# LE.net
KiCad netlist of a schematic drawn in EAGLE
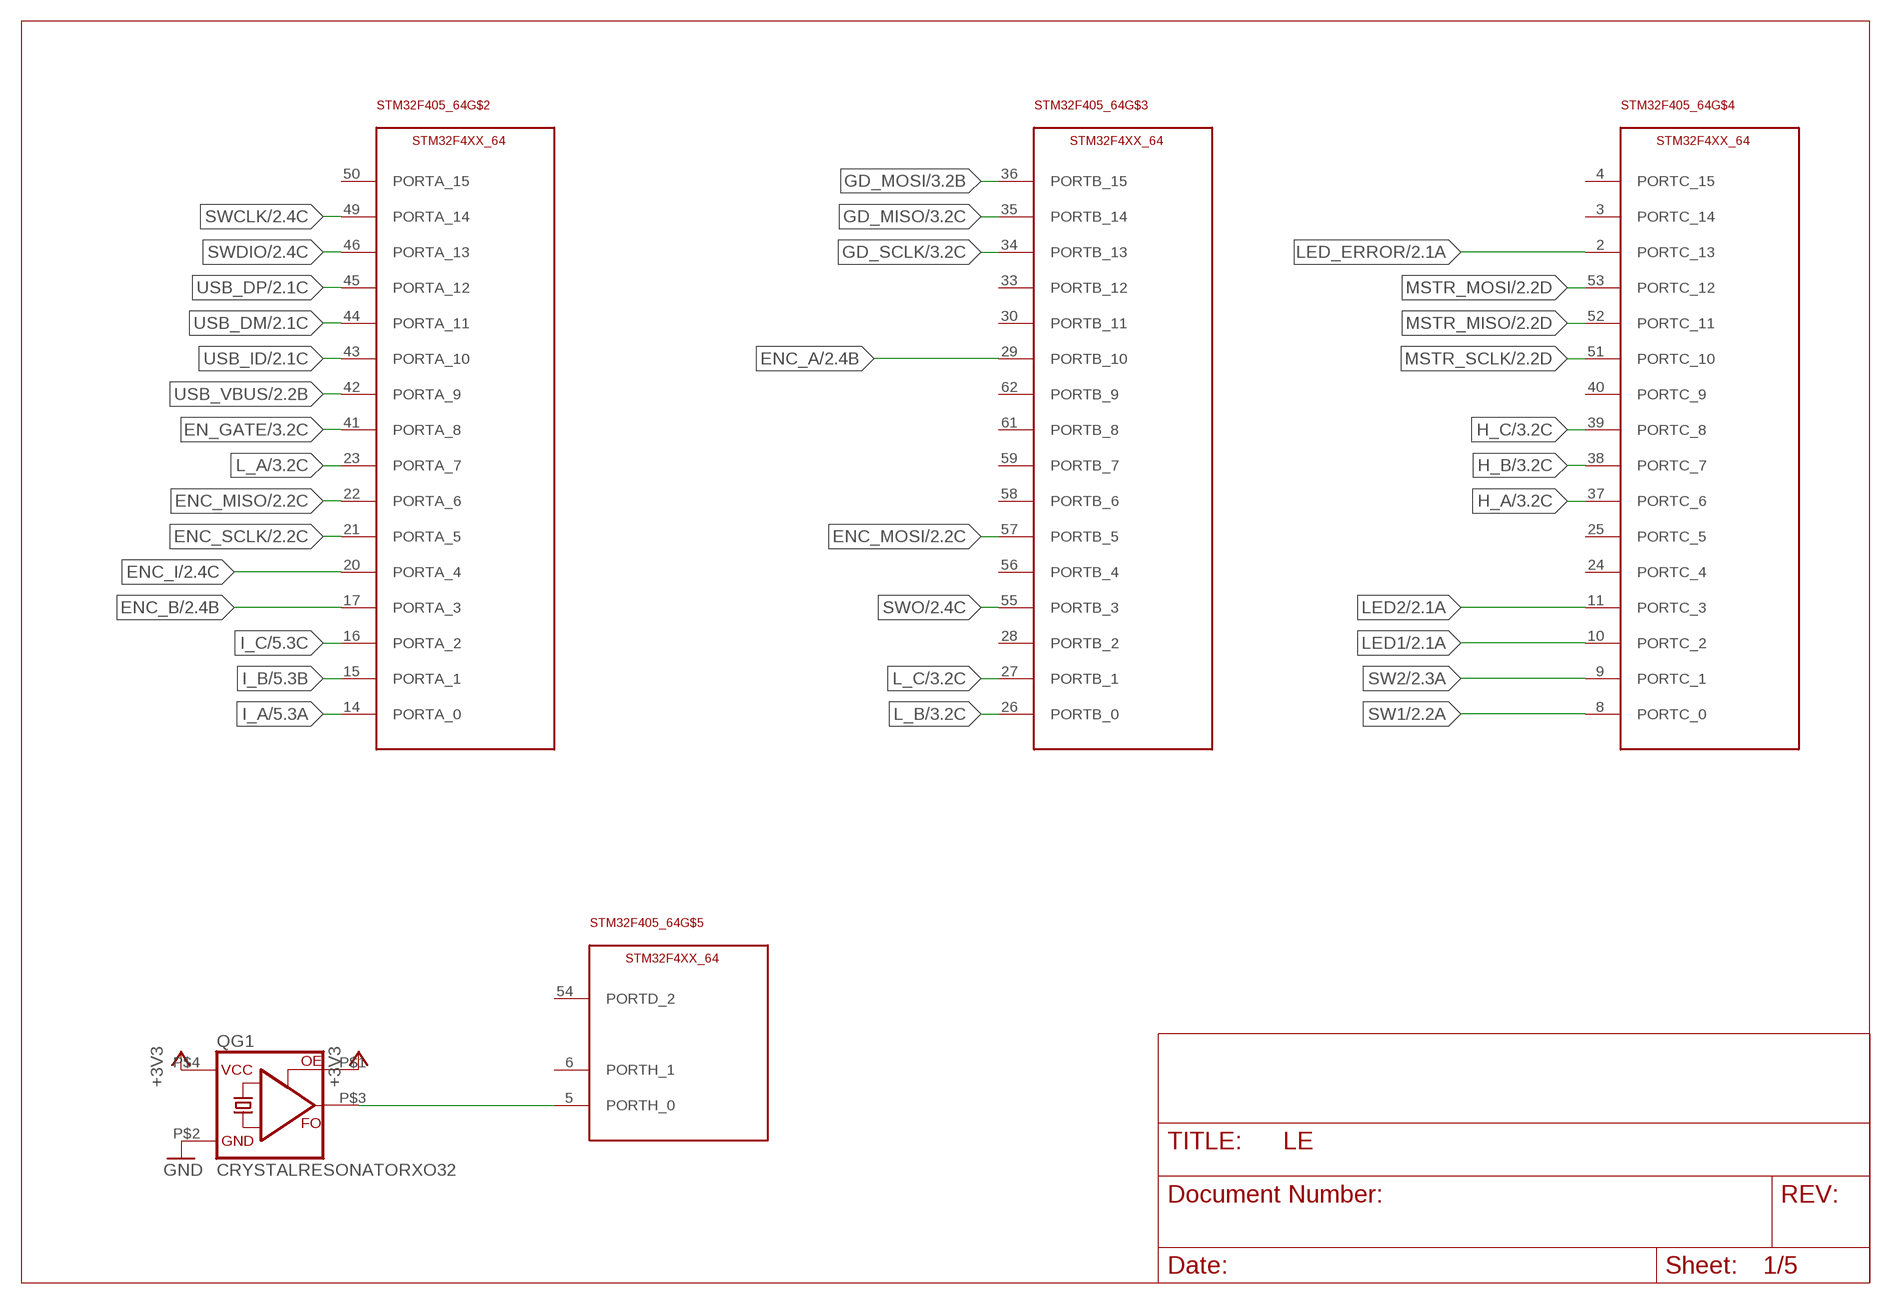
[diagram p0: schematic, sheet 1]
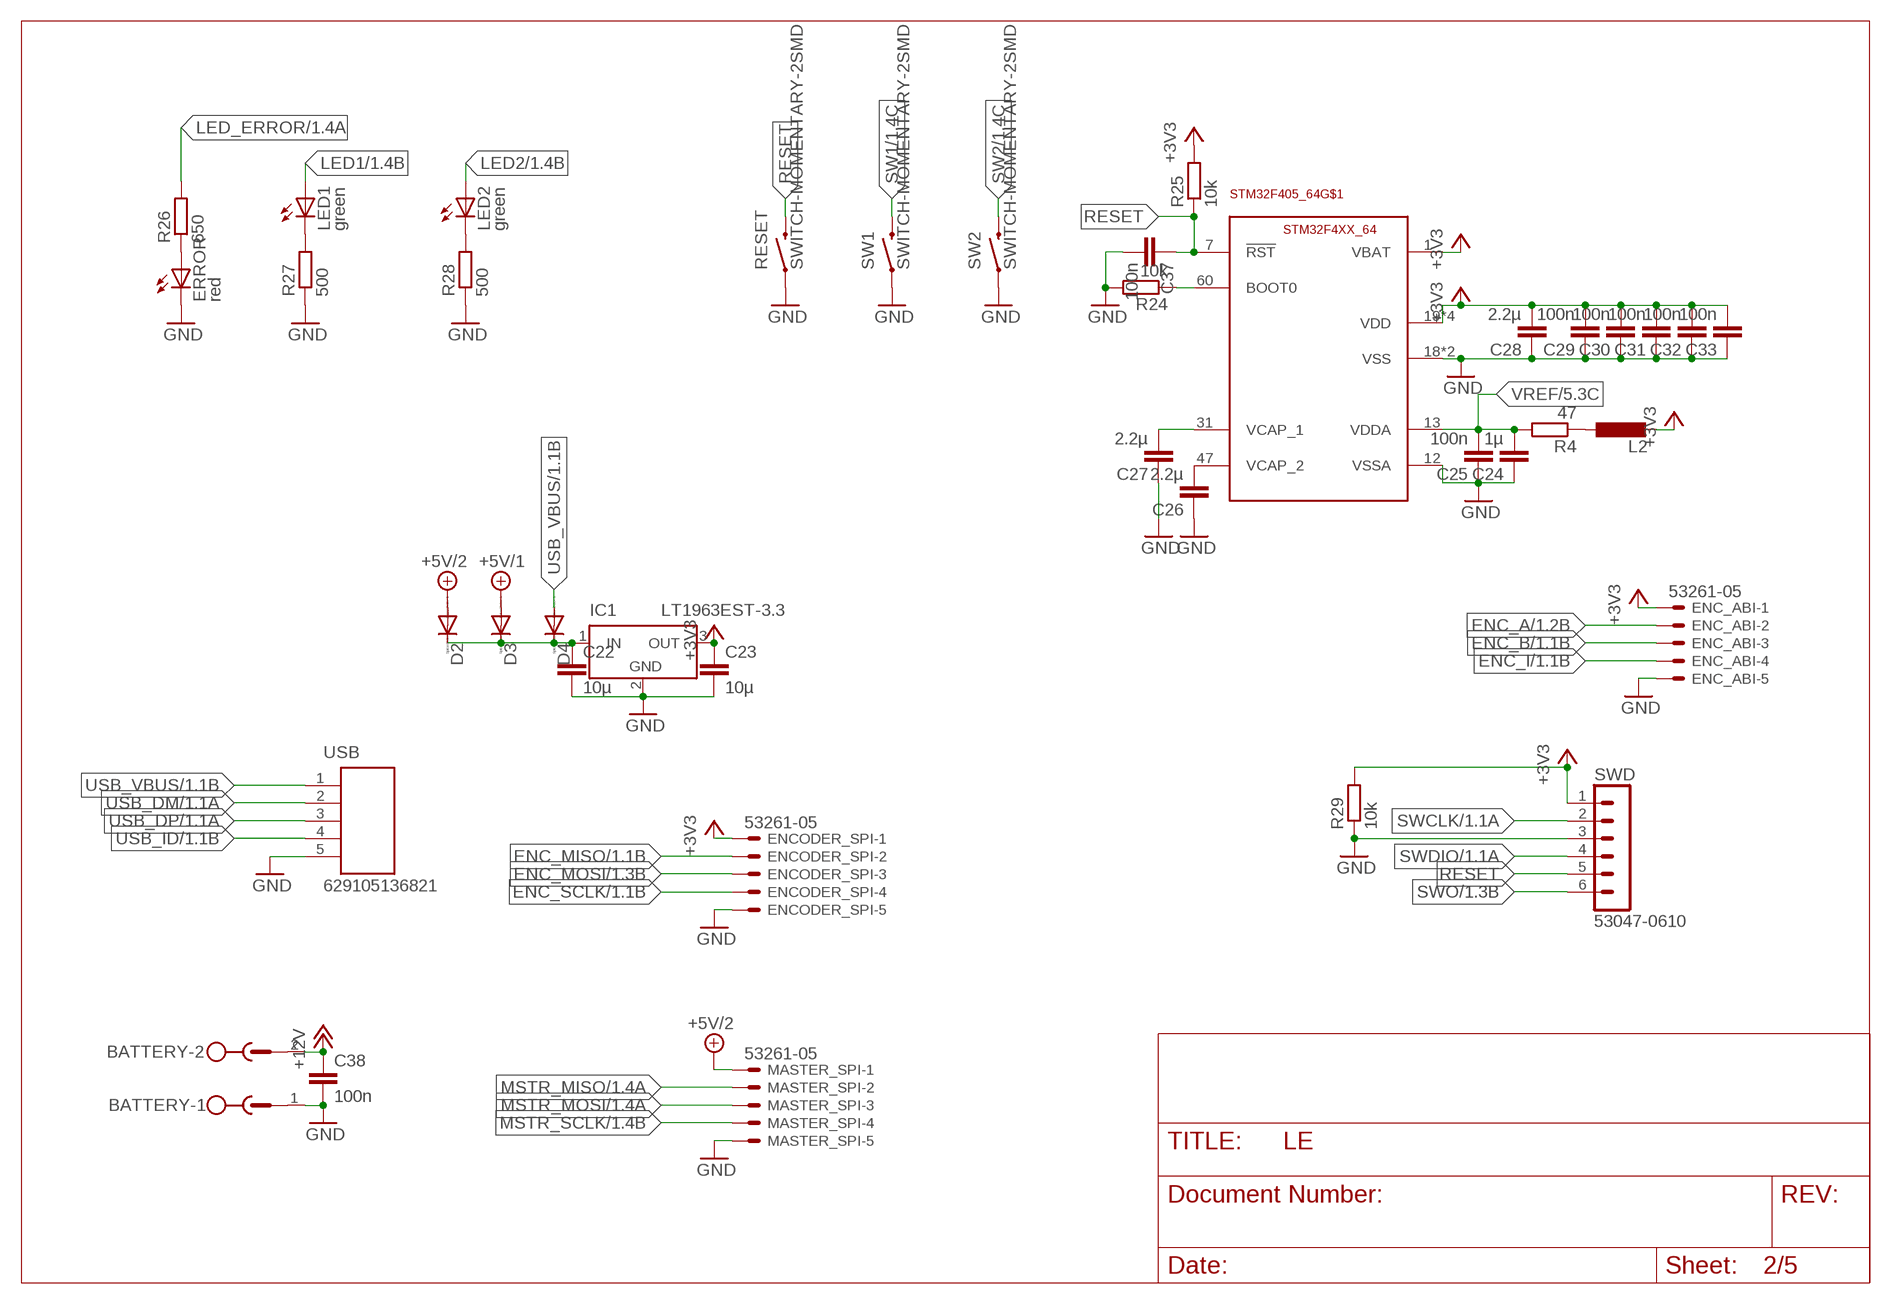
[diagram p1: schematic, sheet 2]
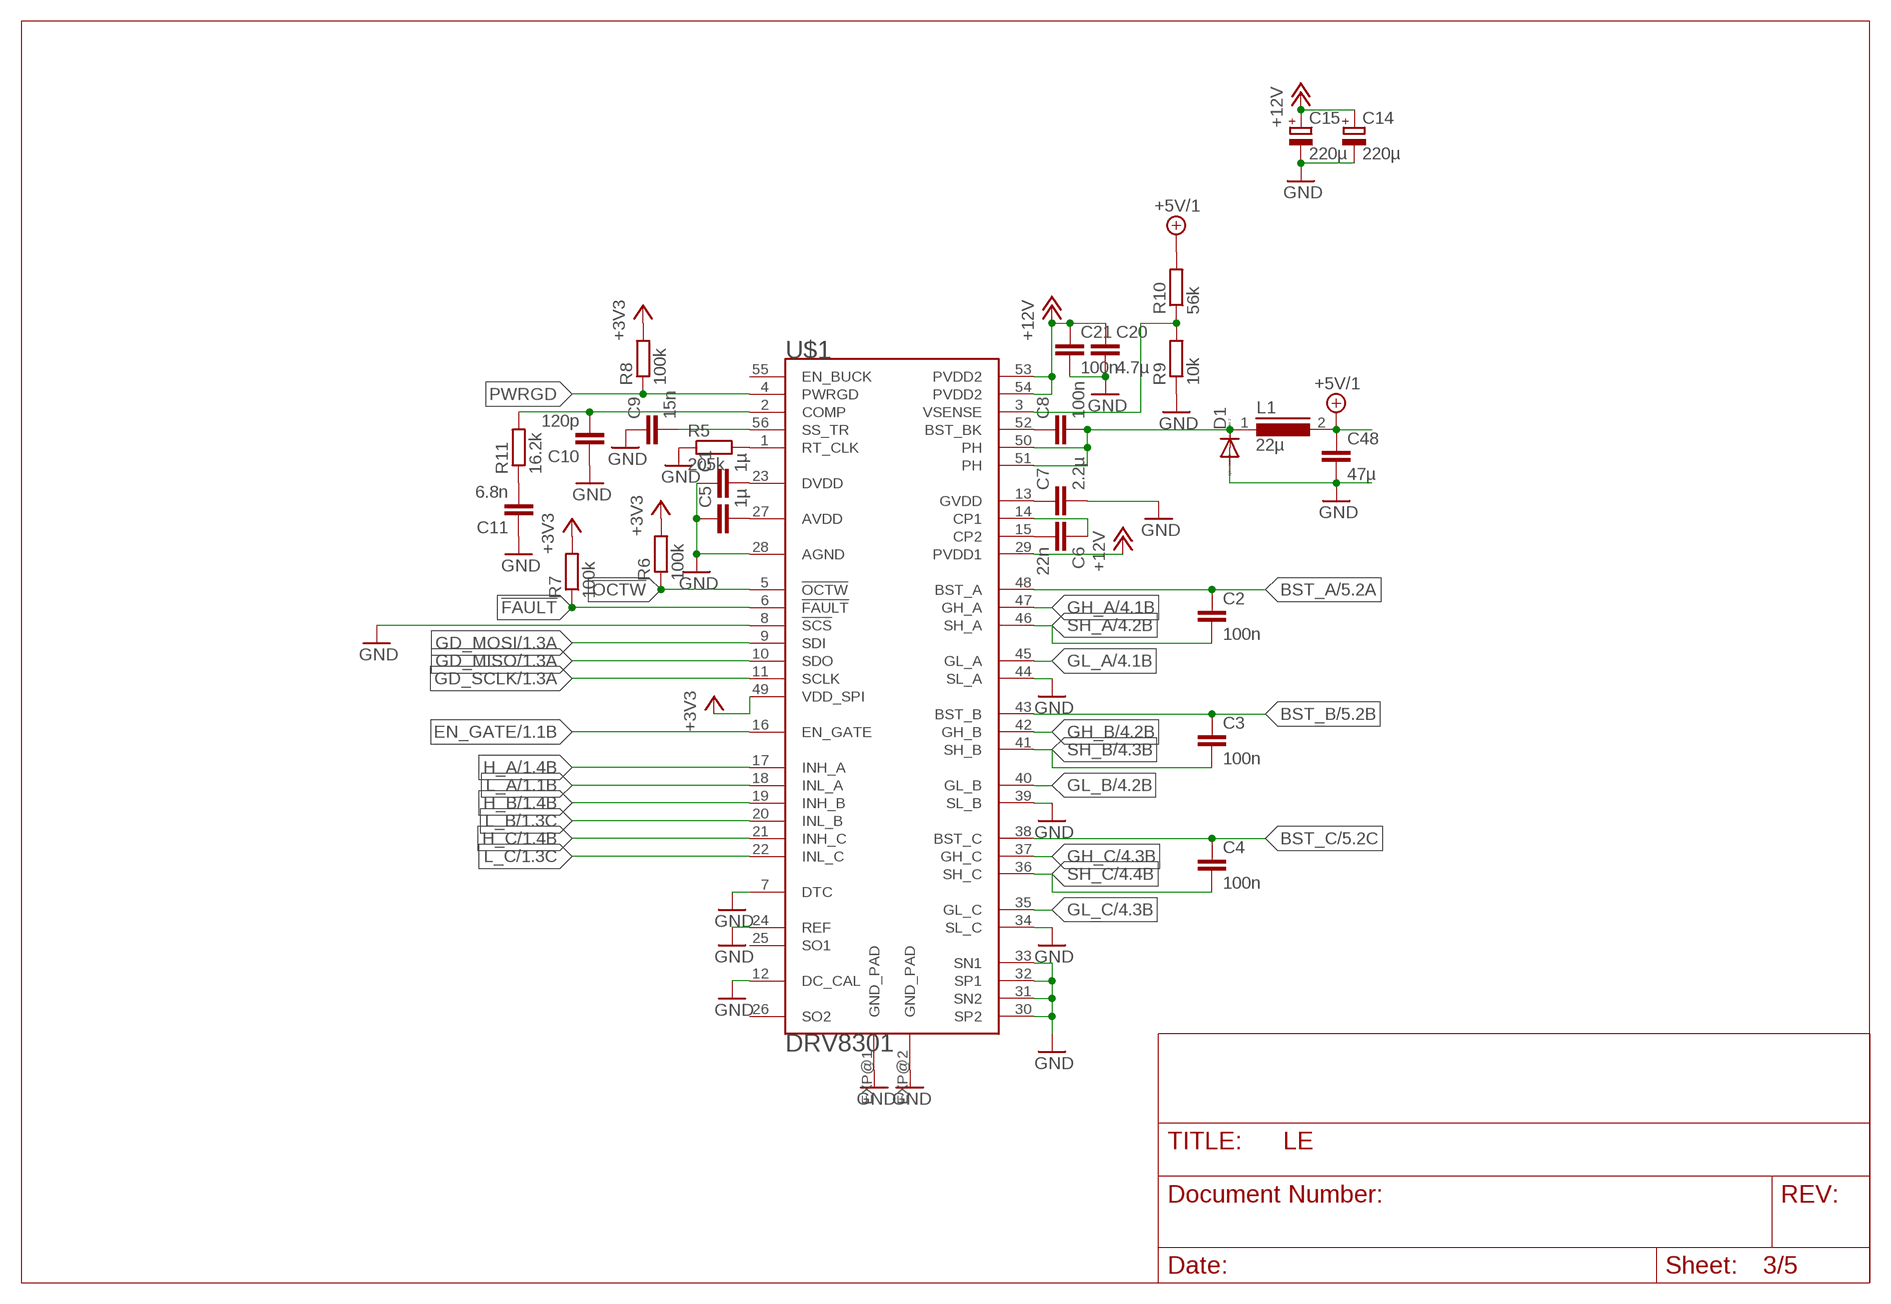
[diagram p2: schematic, sheet 3]
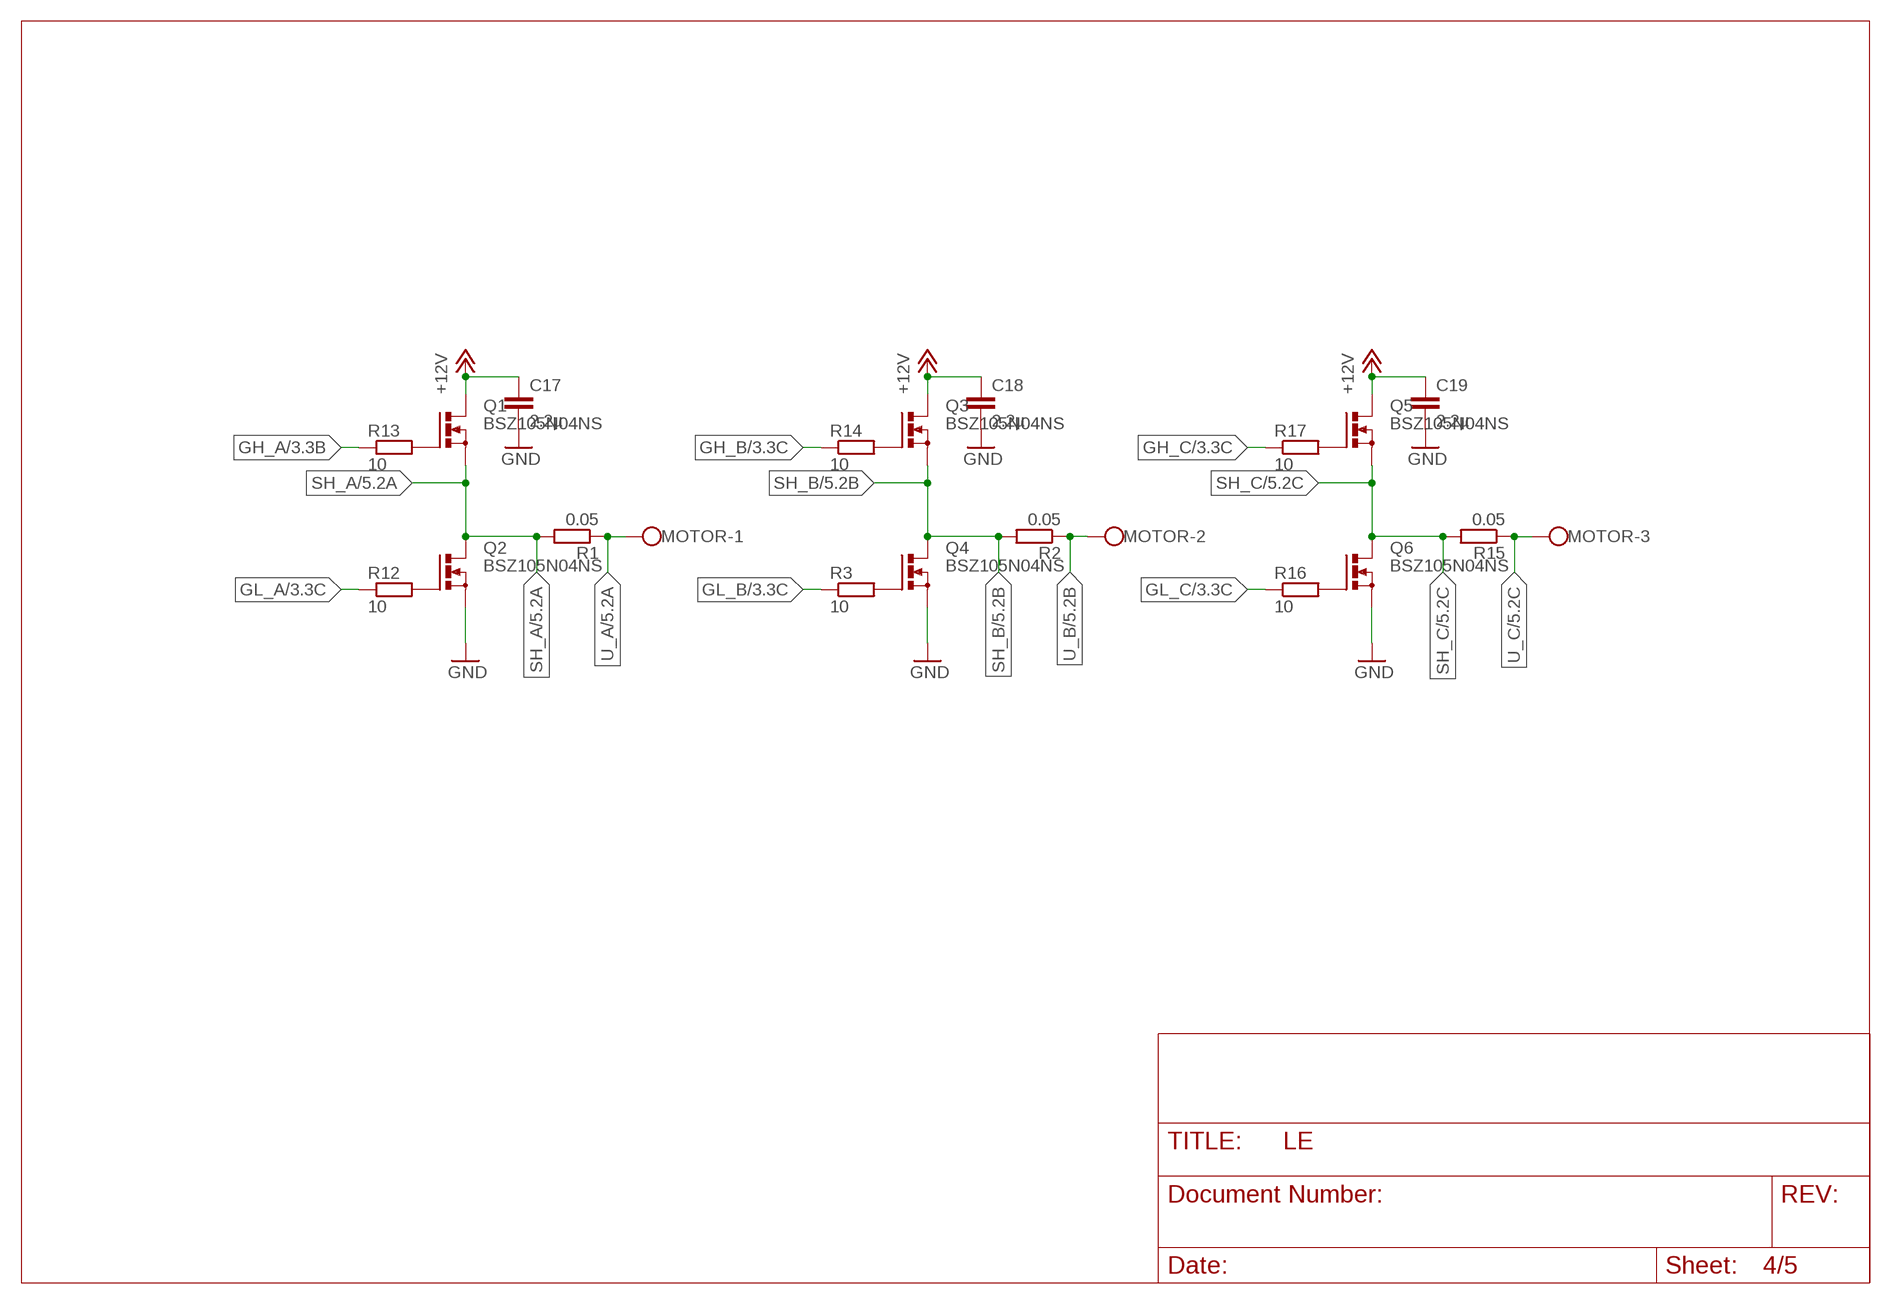
[diagram p3: schematic, sheet 4]
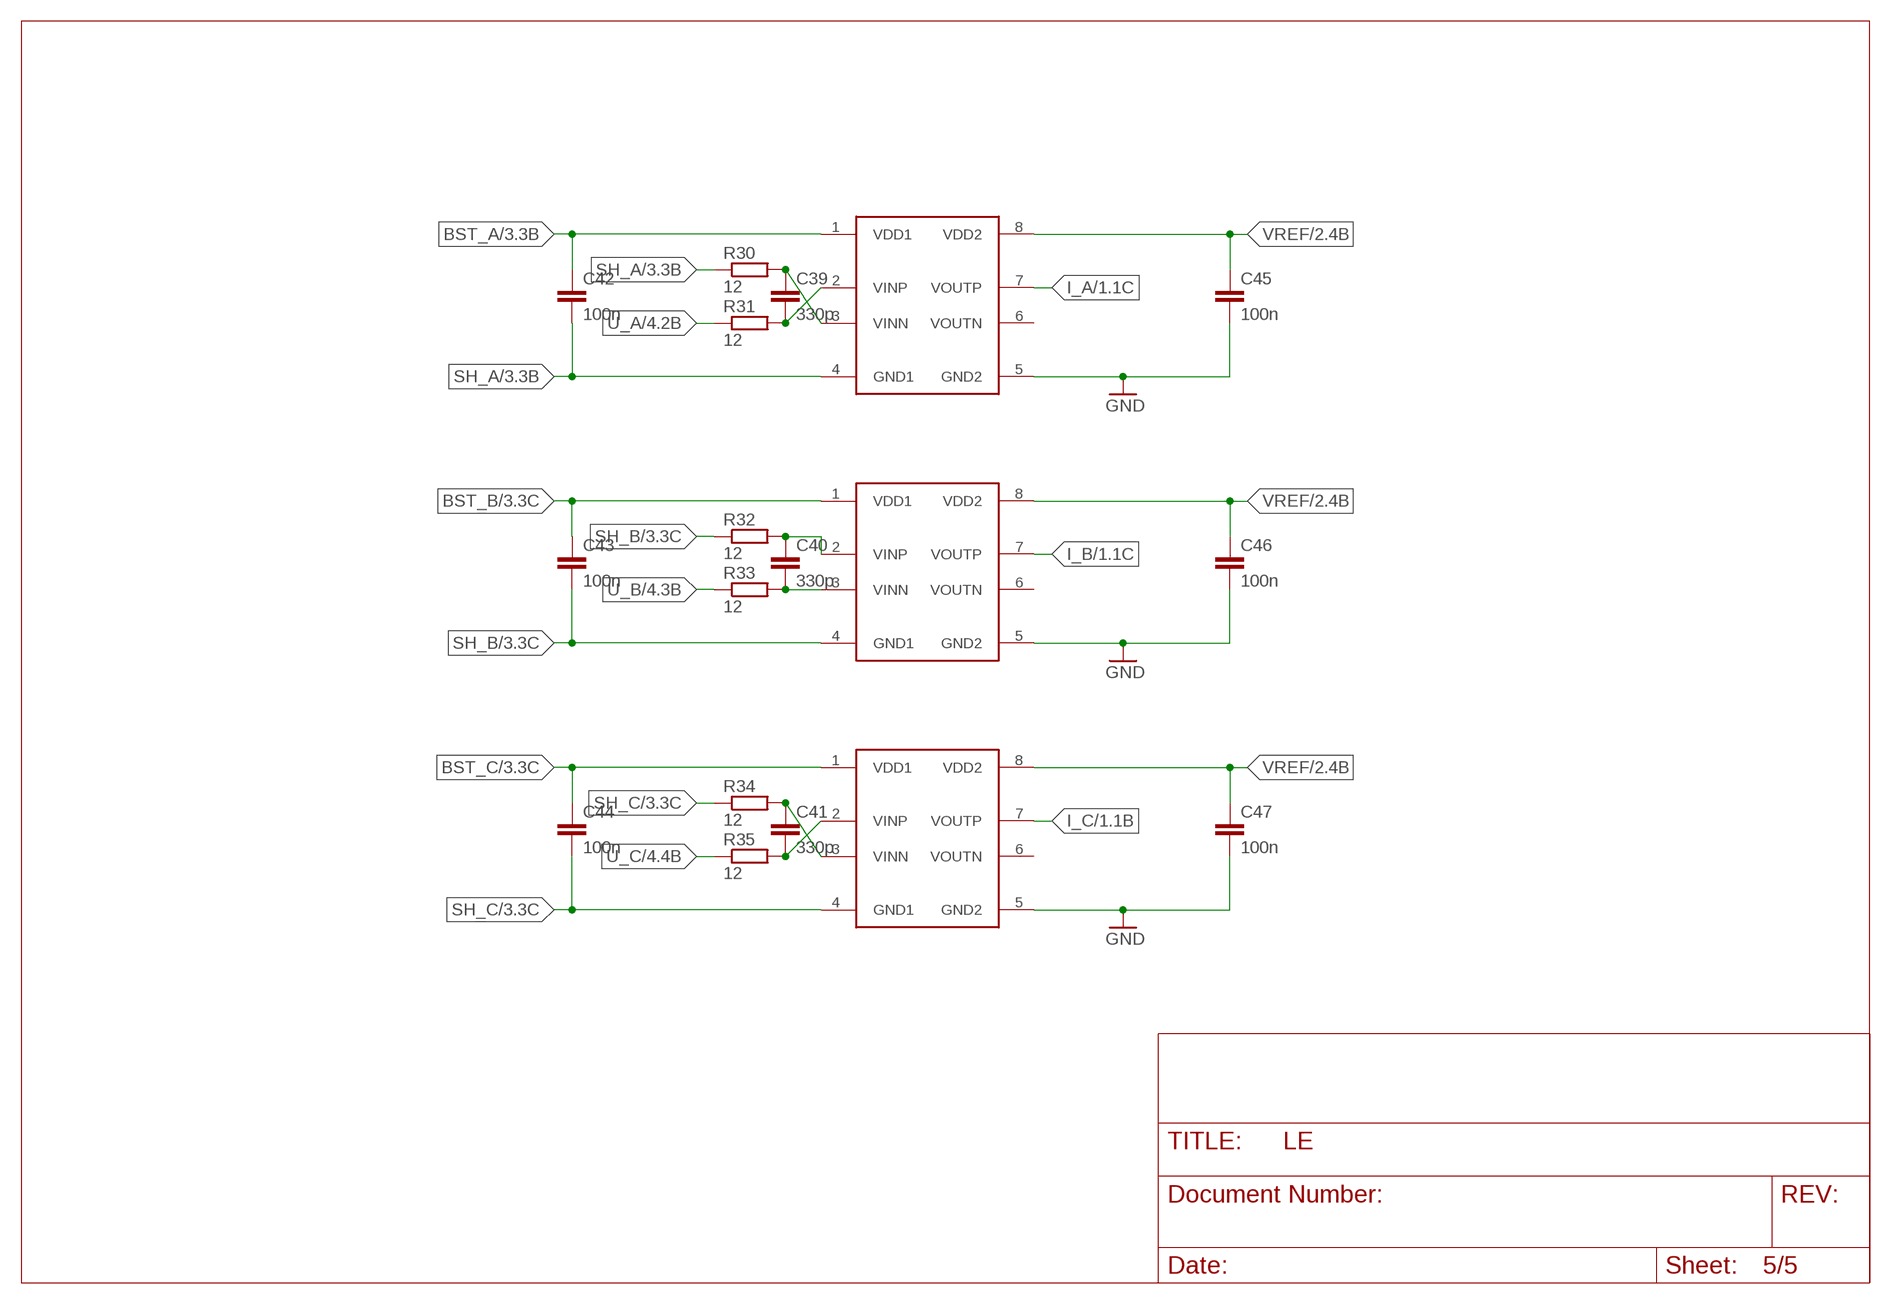
[diagram p4: schematic, sheet 5]

(export (version "E")
  (design (tool "Eeschema 10.0.6"))
  (components
    (comp (ref "C17")
      (value "2.2µ")
      (footprint "eagle-import:C0805")
      (libsource (lib "eagle-import") (part "C-EUC0805"))
    )
    (comp (ref "C18")
      (value "2.2µ")
      (footprint "eagle-import:C0805")
      (libsource (lib "eagle-import") (part "C-EUC0805"))
    )
    (comp (ref "C19")
      (value "2.2µ")
      (footprint "eagle-import:C0805")
      (libsource (lib "eagle-import") (part "C-EUC0805"))
    )
    (comp (ref "MOTOR")
      (value "W237-103")
      (footprint "eagle-import:W237-103")
      (fields (field (name "MPN") "237-103"))
      (libsource (lib "eagle-import") (part "W237-103"))
    )
    (comp (ref "Q1")
      (value "BSZ105N04NS")
      (footprint "eagle-import:PG-TDSON-8")
      (libsource (lib "eagle-import") (part "BSZ105N04NS"))
    )
    (comp (ref "Q2")
      (value "BSZ105N04NS")
      (footprint "eagle-import:PG-TDSON-8")
      (libsource (lib "eagle-import") (part "BSZ105N04NS"))
    )
    (comp (ref "Q3")
      (value "BSZ105N04NS")
      (footprint "eagle-import:PG-TDSON-8")
      (libsource (lib "eagle-import") (part "BSZ105N04NS"))
    )
    (comp (ref "Q4")
      (value "BSZ105N04NS")
      (footprint "eagle-import:PG-TDSON-8")
      (libsource (lib "eagle-import") (part "BSZ105N04NS"))
    )
    (comp (ref "Q5")
      (value "BSZ105N04NS")
      (footprint "eagle-import:PG-TDSON-8")
      (libsource (lib "eagle-import") (part "BSZ105N04NS"))
    )
    (comp (ref "Q6")
      (value "BSZ105N04NS")
      (footprint "eagle-import:PG-TDSON-8")
      (libsource (lib "eagle-import") (part "BSZ105N04NS"))
    )
    (comp (ref "R1")
      (value "0.05")
      (footprint "eagle-import:R1206")
      (libsource (lib "eagle-import") (part "R-EU_R1206"))
    )
    (comp (ref "R2")
      (value "0.05")
      (footprint "eagle-import:R1206")
      (libsource (lib "eagle-import") (part "R-EU_R1206"))
    )
    (comp (ref "R3")
      (value "10")
      (footprint "eagle-import:R1206")
      (libsource (lib "eagle-import") (part "R-EU_R1206"))
    )
    (comp (ref "R12")
      (value "10")
      (footprint "eagle-import:R1206")
      (libsource (lib "eagle-import") (part "R-EU_R1206"))
    )
    (comp (ref "R13")
      (value "10")
      (footprint "eagle-import:R0805")
      (libsource (lib "eagle-import") (part "R-EU_R0805"))
    )
    (comp (ref "R14")
      (value "10")
      (footprint "eagle-import:R0805")
      (libsource (lib "eagle-import") (part "R-EU_R0805"))
    )
    (comp (ref "R15")
      (value "0.05")
      (footprint "eagle-import:R1206")
      (libsource (lib "eagle-import") (part "R-EU_R1206"))
    )
    (comp (ref "R16")
      (value "10")
      (footprint "eagle-import:R1206")
      (libsource (lib "eagle-import") (part "R-EU_R1206"))
    )
    (comp (ref "R17")
      (value "10")
      (footprint "eagle-import:R0805")
      (libsource (lib "eagle-import") (part "R-EU_R0805"))
    )
    (comp (ref "C39")
      (value "330p")
      (footprint "eagle-import:C0805")
      (libsource (lib "eagle-import") (part "C-EUC0805"))
    )
    (comp (ref "C40")
      (value "330p")
      (footprint "eagle-import:C0805")
      (libsource (lib "eagle-import") (part "C-EUC0805"))
    )
    (comp (ref "C41")
      (value "330p")
      (footprint "eagle-import:C0805")
      (libsource (lib "eagle-import") (part "C-EUC0805"))
    )
    (comp (ref "C42")
      (value "100n")
      (footprint "eagle-import:C1206")
      (libsource (lib "eagle-import") (part "C-EUC1206"))
    )
    (comp (ref "C43")
      (value "100n")
      (footprint "eagle-import:C1206")
      (libsource (lib "eagle-import") (part "C-EUC1206"))
    )
    (comp (ref "C44")
      (value "100n")
      (footprint "eagle-import:C1206")
      (libsource (lib "eagle-import") (part "C-EUC1206"))
    )
    (comp (ref "C45")
      (value "100n")
      (footprint "eagle-import:C1206")
      (libsource (lib "eagle-import") (part "C-EUC1206"))
    )
    (comp (ref "C46")
      (value "100n")
      (footprint "eagle-import:C1206")
      (libsource (lib "eagle-import") (part "C-EUC1206"))
    )
    (comp (ref "C47")
      (value "100n")
      (footprint "eagle-import:C1206")
      (libsource (lib "eagle-import") (part "C-EUC1206"))
    )
    (comp (ref "R30")
      (value "12")
      (footprint "eagle-import:R0805")
      (libsource (lib "eagle-import") (part "R-EU_R0805"))
    )
    (comp (ref "R31")
      (value "12")
      (footprint "eagle-import:R0805")
      (libsource (lib "eagle-import") (part "R-EU_R0805"))
    )
    (comp (ref "R32")
      (value "12")
      (footprint "eagle-import:R0805")
      (libsource (lib "eagle-import") (part "R-EU_R0805"))
    )
    (comp (ref "R33")
      (value "12")
      (footprint "eagle-import:R0805")
      (libsource (lib "eagle-import") (part "R-EU_R0805"))
    )
    (comp (ref "R34")
      (value "12")
      (footprint "eagle-import:R0805")
      (libsource (lib "eagle-import") (part "R-EU_R0805"))
    )
    (comp (ref "R35")
      (value "12")
      (footprint "eagle-import:R0805")
      (libsource (lib "eagle-import") (part "R-EU_R0805"))
    )
    (comp (ref "U$2")
      (value "AMC1200")
      (footprint "eagle-import:SOIC8")
      (libsource (lib "eagle-import") (part "AMC1200"))
    )
    (comp (ref "U$3")
      (value "AMC1200")
      (footprint "eagle-import:SOIC8")
      (libsource (lib "eagle-import") (part "AMC1200"))
    )
    (comp (ref "U$4")
      (value "AMC1200")
      (footprint "eagle-import:SOIC8")
      (libsource (lib "eagle-import") (part "AMC1200"))
    )
    (comp (ref "BATTERY")
      (value "MSTBV2")
      (footprint "eagle-import:MSTBV2")
      (libsource (lib "eagle-import") (part "MSTBV2"))
    )
    (comp (ref "C22")
      (value "10µ")
      (footprint "eagle-import:C0805")
      (libsource (lib "eagle-import") (part "C-EUC0805"))
    )
    (comp (ref "C23")
      (value "10µ")
      (footprint "eagle-import:C0805")
      (libsource (lib "eagle-import") (part "C-EUC0805"))
    )
    (comp (ref "C24")
      (value "1µ")
      (footprint "eagle-import:C0805")
      (libsource (lib "eagle-import") (part "C-EUC0805"))
    )
    (comp (ref "C25")
      (value "100n")
      (footprint "eagle-import:C0805")
      (libsource (lib "eagle-import") (part "C-EUC0805"))
    )
    (comp (ref "C26")
      (value "2.2µ")
      (footprint "eagle-import:C0805")
      (libsource (lib "eagle-import") (part "C-EUC0805"))
    )
    (comp (ref "C27")
      (value "2.2µ")
      (footprint "eagle-import:C0805")
      (libsource (lib "eagle-import") (part "C-EUC0805"))
    )
    (comp (ref "C28")
      (value "2.2µ")
      (footprint "eagle-import:C0805")
      (libsource (lib "eagle-import") (part "C-EUC0805"))
    )
    (comp (ref "C29")
      (value "100n")
      (footprint "eagle-import:C0805")
      (libsource (lib "eagle-import") (part "C-EUC0805"))
    )
    (comp (ref "C30")
      (value "100n")
      (footprint "eagle-import:C0805")
      (libsource (lib "eagle-import") (part "C-EUC0805"))
    )
    (comp (ref "C31")
      (value "100n")
      (footprint "eagle-import:C0805")
      (libsource (lib "eagle-import") (part "C-EUC0805"))
    )
    (comp (ref "C32")
      (value "100n")
      (footprint "eagle-import:C0805")
      (libsource (lib "eagle-import") (part "C-EUC0805"))
    )
    (comp (ref "C33")
      (value "100n")
      (footprint "eagle-import:C0805")
      (libsource (lib "eagle-import") (part "C-EUC0805"))
    )
    (comp (ref "C37")
      (value "100n")
      (footprint "eagle-import:C0805")
      (libsource (lib "eagle-import") (part "C-EUC0805"))
    )
    (comp (ref "C38")
      (value "100n")
      (footprint "eagle-import:C0805")
      (libsource (lib "eagle-import") (part "C-EUC0805"))
    )
    (comp (ref "D2")
      (value "DIODE-DO214AC")
      (footprint "eagle-import:DO214AC")
      (libsource (lib "eagle-import") (part "DIODE-DO214AC"))
    )
    (comp (ref "D3")
      (value "DIODE-DO214AC")
      (footprint "eagle-import:DO214AC")
      (libsource (lib "eagle-import") (part "DIODE-DO214AC"))
    )
    (comp (ref "D4")
      (value "DIODE-DO214AC")
      (footprint "eagle-import:DO214AC")
      (libsource (lib "eagle-import") (part "DIODE-DO214AC"))
    )
    (comp (ref "ENCODER_SPI")
      (value "53261-05")
      (footprint "eagle-import:53261-05")
      (libsource (lib "eagle-import") (part "53?-05261"))
    )
    (comp (ref "ENC_ABI")
      (value "53261-05")
      (footprint "eagle-import:53261-05")
      (libsource (lib "eagle-import") (part "53?-05261"))
    )
    (comp (ref "ERROR")
      (value "red")
      (footprint "eagle-import:CHIP-LED0805")
      (libsource (lib "eagle-import") (part "LEDCHIP-LED0805"))
    )
    (comp (ref "IC1")
      (value "LT1963EST-3.3")
      (footprint "eagle-import:SOT223")
      (libsource (lib "eagle-import") (part "LT1963EST-3.3"))
    )
    (comp (ref "L2")
      (value "L-EUL2012C")
      (footprint "eagle-import:L2012C")
      (libsource (lib "eagle-import") (part "L-EUL2012C"))
    )
    (comp (ref "LED1")
      (value "green")
      (footprint "eagle-import:CHIP-LED0805")
      (libsource (lib "eagle-import") (part "LEDCHIP-LED0805"))
    )
    (comp (ref "LED2")
      (value "green")
      (footprint "eagle-import:CHIP-LED0805")
      (libsource (lib "eagle-import") (part "LEDCHIP-LED0805"))
    )
    (comp (ref "MASTER_SPI")
      (value "53261-05")
      (footprint "eagle-import:53261-05")
      (libsource (lib "eagle-import") (part "53?-05261"))
    )
    (comp (ref "R4")
      (value "47")
      (footprint "eagle-import:R0805")
      (libsource (lib "eagle-import") (part "R-EU_R0805"))
    )
    (comp (ref "R24")
      (value "10k")
      (footprint "eagle-import:R0805")
      (libsource (lib "eagle-import") (part "R-EU_R0805"))
    )
    (comp (ref "R25")
      (value "10k")
      (footprint "eagle-import:R0805")
      (libsource (lib "eagle-import") (part "R-EU_R0805"))
    )
    (comp (ref "R26")
      (value "650")
      (footprint "eagle-import:R0805")
      (libsource (lib "eagle-import") (part "R-EU_R0805"))
    )
    (comp (ref "R27")
      (value "500")
      (footprint "eagle-import:R0805")
      (libsource (lib "eagle-import") (part "R-EU_R0805"))
    )
    (comp (ref "R28")
      (value "500")
      (footprint "eagle-import:R0805")
      (libsource (lib "eagle-import") (part "R-EU_R0805"))
    )
    (comp (ref "R29")
      (value "10k")
      (footprint "eagle-import:R0805")
      (libsource (lib "eagle-import") (part "R-EU_R0805"))
    )
    (comp (ref "RESET")
      (value "SWITCH-MOMENTARY-2SMD")
      (footprint "eagle-import:TACTILE-SWITCH-SMD")
      (libsource (lib "eagle-import") (part "SWITCH-MOMENTARY-2SMD"))
    )
    (comp (ref "STM32F405_64")
      (value "STM32F4XX_64")
      (footprint "eagle-import:TQFP64")
      (libsource (lib "eagle-import") (part "STM32F4XX_64"))
    )
    (comp (ref "SW1")
      (value "SWITCH-MOMENTARY-2SMD")
      (footprint "eagle-import:TACTILE-SWITCH-SMD")
      (libsource (lib "eagle-import") (part "SWITCH-MOMENTARY-2SMD"))
    )
    (comp (ref "SW2")
      (value "SWITCH-MOMENTARY-2SMD")
      (footprint "eagle-import:TACTILE-SWITCH-SMD")
      (libsource (lib "eagle-import") (part "SWITCH-MOMENTARY-2SMD"))
    )
    (comp (ref "SWD")
      (value "53047-0610")
      (footprint "eagle-import:53047-0610")
      (libsource (lib "eagle-import") (part "53047-0610"))
    )
    (comp (ref "USB")
      (value "629105136821")
      (footprint "eagle-import:629105136821")
      (libsource (lib "eagle-import") (part "629105136821"))
    )
    (comp (ref "C1")
      (value "1µ")
      (footprint "eagle-import:C0805")
      (libsource (lib "eagle-import") (part "C-EUC0805"))
    )
    (comp (ref "C2")
      (value "100n")
      (footprint "eagle-import:C0805")
      (libsource (lib "eagle-import") (part "C-EUC0805"))
    )
    (comp (ref "C3")
      (value "100n")
      (footprint "eagle-import:C0805")
      (libsource (lib "eagle-import") (part "C-EUC0805"))
    )
    (comp (ref "C4")
      (value "100n")
      (footprint "eagle-import:C0805")
      (libsource (lib "eagle-import") (part "C-EUC0805"))
    )
    (comp (ref "C5")
      (value "1µ")
      (footprint "eagle-import:C0805")
      (libsource (lib "eagle-import") (part "C-EUC0805"))
    )
    (comp (ref "C6")
      (value "22n")
      (footprint "eagle-import:C0805")
      (libsource (lib "eagle-import") (part "C-EUC0805"))
    )
    (comp (ref "C7")
      (value "2.2µ")
      (footprint "eagle-import:C0805")
      (libsource (lib "eagle-import") (part "C-EUC0805"))
    )
    (comp (ref "C8")
      (value "100n")
      (footprint "eagle-import:C0805")
      (libsource (lib "eagle-import") (part "C-EUC0805"))
    )
    (comp (ref "C9")
      (value "15n")
      (footprint "eagle-import:C0805")
      (libsource (lib "eagle-import") (part "C-EUC0805"))
    )
    (comp (ref "C10")
      (value "120p")
      (footprint "eagle-import:C0805")
      (libsource (lib "eagle-import") (part "C-EUC0805"))
    )
    (comp (ref "C11")
      (value "6.8n")
      (footprint "eagle-import:C0805")
      (libsource (lib "eagle-import") (part "C-EUC0805"))
    )
    (comp (ref "C14")
      (value "220µ")
      (footprint "eagle-import:PANASONIC_G")
      (libsource (lib "eagle-import") (part "CPOL-EUG"))
    )
    (comp (ref "C15")
      (value "220µ")
      (footprint "eagle-import:PANASONIC_G")
      (libsource (lib "eagle-import") (part "CPOL-EUG"))
    )
    (comp (ref "C20")
      (value "4.7µ")
      (footprint "eagle-import:C0805")
      (libsource (lib "eagle-import") (part "C-EUC0805"))
    )
    (comp (ref "C21")
      (value "100n")
      (footprint "eagle-import:C0805")
      (libsource (lib "eagle-import") (part "C-EUC0805"))
    )
    (comp (ref "C48")
      (value "47µ")
      (footprint "eagle-import:C1206")
      (libsource (lib "eagle-import") (part "C-EUC1206"))
    )
    (comp (ref "D1")
      (value "DIODE-DO-214AC")
      (footprint "eagle-import:DO-214AC")
      (libsource (lib "eagle-import") (part "DIODE-DO-214AC"))
    )
    (comp (ref "L1")
      (value "22µ")
      (footprint "eagle-import:DR127")
      (libsource (lib "eagle-import") (part "DR127"))
    )
    (comp (ref "R5")
      (value "205k")
      (footprint "eagle-import:R0805")
      (libsource (lib "eagle-import") (part "R-EU_R0805"))
    )
    (comp (ref "R6")
      (value "100k")
      (footprint "eagle-import:R0805")
      (libsource (lib "eagle-import") (part "R-EU_R0805"))
    )
    (comp (ref "R7")
      (value "100k")
      (footprint "eagle-import:R0805")
      (libsource (lib "eagle-import") (part "R-EU_R0805"))
    )
    (comp (ref "R8")
      (value "100k")
      (footprint "eagle-import:R0805")
      (libsource (lib "eagle-import") (part "R-EU_R0805"))
    )
    (comp (ref "R9")
      (value "10k")
      (footprint "eagle-import:R0805")
      (libsource (lib "eagle-import") (part "R-EU_R0805"))
    )
    (comp (ref "R10")
      (value "56k")
      (footprint "eagle-import:R0805")
      (libsource (lib "eagle-import") (part "R-EU_R0805"))
    )
    (comp (ref "R11")
      (value "16.2k")
      (footprint "eagle-import:R0805")
      (libsource (lib "eagle-import") (part "R-EU_R0805"))
    )
    (comp (ref "U$1")
      (value "DRV8301")
      (footprint "eagle-import:HTSSOP56DCA")
      (libsource (lib "eagle-import") (part "DRV8301"))
    )
    (comp (ref "QG1")
      (value "CRYSTALRESONATORXO32")
      (footprint "eagle-import:XO32")
      (libsource (lib "eagle-import") (part "CRYSTALRESONATORXO32"))
    )
  )
  (nets
    (net (code "1") (name "+3V3") (class "Default")
      (node (ref "C23") (pin "1") (pinfunction "1_1") (pintype "passive"))
      (node (ref "C28") (pin "2") (pinfunction "2_2") (pintype "passive"))
      (node (ref "C29") (pin "2") (pinfunction "2_2") (pintype "passive"))
      (node (ref "C30") (pin "2") (pinfunction "2_2") (pintype "passive"))
      (node (ref "C31") (pin "2") (pinfunction "2_2") (pintype "passive"))
      (node (ref "C32") (pin "2") (pinfunction "2_2") (pintype "passive"))
      (node (ref "C33") (pin "2") (pinfunction "2_2") (pintype "passive"))
      (node (ref "ENCODER_SPI") (pin "1") (pinfunction "S_1") (pintype "passive"))
      (node (ref "ENC_ABI") (pin "1") (pinfunction "S_1") (pintype "passive"))
      (node (ref "IC1") (pin "3") (pinfunction "OUT_3") (pintype "output"))
      (node (ref "L2") (pin "2") (pinfunction "2_2") (pintype "passive"))
      (node (ref "QG1") (pin "P$1") (pinfunction "OE_P$1") (pintype "input"))
      (node (ref "QG1") (pin "P$4") (pinfunction "VCC_P$4") (pintype "power_in"))
      (node (ref "R25") (pin "2") (pinfunction "2_2") (pintype "passive"))
      (node (ref "R29") (pin "2") (pinfunction "2_2") (pintype "passive"))
      (node (ref "R6") (pin "2") (pinfunction "2_2") (pintype "passive"))
      (node (ref "R7") (pin "2") (pinfunction "2_2") (pintype "passive"))
      (node (ref "R8") (pin "2") (pinfunction "2_2") (pintype "passive"))
      (node (ref "STM32F405_64") (pin "1") (pinfunction "VBAT_1") (pintype "bidirectional"))
      (node (ref "STM32F405_64") (pin "19") (pinfunction "VDD_19") (pintype "bidirectional"))
      (node (ref "STM32F405_64") (pin "32") (pinfunction "VDD_32") (pintype "bidirectional"))
      (node (ref "STM32F405_64") (pin "48") (pinfunction "VDD_48") (pintype "bidirectional"))
      (node (ref "STM32F405_64") (pin "64") (pinfunction "VDD_64") (pintype "bidirectional"))
      (node (ref "SWD") (pin "1") (pinfunction "1_1") (pintype "passive"))
      (node (ref "U$1") (pin "49") (pinfunction "VDD_SPI_49") (pintype "bidirectional"))
    )
    (net (code "2") (name "+5V{slash}1") (class "Default")
      (node (ref "C48") (pin "1") (pinfunction "1_1") (pintype "passive"))
      (node (ref "D3") (pin "A") (pinfunction "A_A") (pintype "passive"))
      (node (ref "L1") (pin "2") (pinfunction "2_2") (pintype "passive"))
      (node (ref "R10") (pin "2") (pinfunction "2_2") (pintype "passive"))
    )
    (net (code "3") (name "+5V{slash}2") (class "Default")
      (node (ref "D2") (pin "A") (pinfunction "A_A") (pintype "passive"))
      (node (ref "MASTER_SPI") (pin "1") (pinfunction "S_1") (pintype "passive"))
    )
    (net (code "4") (name "+12V") (class "Default")
      (node (ref "BATTERY") (pin "2") (pinfunction "SK_2") (pintype "passive"))
      (node (ref "C14") (pin "+") (pinfunction "+_+") (pintype "passive"))
      (node (ref "C15") (pin "+") (pinfunction "+_+") (pintype "passive"))
      (node (ref "C17") (pin "1") (pinfunction "1_1") (pintype "passive"))
      (node (ref "C18") (pin "1") (pinfunction "1_1") (pintype "passive"))
      (node (ref "C19") (pin "1") (pinfunction "1_1") (pintype "passive"))
      (node (ref "C20") (pin "1") (pinfunction "1_1") (pintype "passive"))
      (node (ref "C21") (pin "1") (pinfunction "1_1") (pintype "passive"))
      (node (ref "C38") (pin "1") (pinfunction "1_1") (pintype "passive"))
      (node (ref "Q1") (pin "5") (pinfunction "D_5") (pintype "passive"))
      (node (ref "Q1") (pin "6") (pinfunction "D_6") (pintype "passive"))
      (node (ref "Q1") (pin "7") (pinfunction "D_7") (pintype "passive"))
      (node (ref "Q1") (pin "8") (pinfunction "D_8") (pintype "passive"))
      (node (ref "Q1") (pin "TH") (pinfunction "D_TH") (pintype "passive"))
      (node (ref "Q3") (pin "5") (pinfunction "D_5") (pintype "passive"))
      (node (ref "Q3") (pin "6") (pinfunction "D_6") (pintype "passive"))
      (node (ref "Q3") (pin "7") (pinfunction "D_7") (pintype "passive"))
      (node (ref "Q3") (pin "8") (pinfunction "D_8") (pintype "passive"))
      (node (ref "Q3") (pin "TH") (pinfunction "D_TH") (pintype "passive"))
      (node (ref "Q5") (pin "5") (pinfunction "D_5") (pintype "passive"))
      (node (ref "Q5") (pin "6") (pinfunction "D_6") (pintype "passive"))
      (node (ref "Q5") (pin "7") (pinfunction "D_7") (pintype "passive"))
      (node (ref "Q5") (pin "8") (pinfunction "D_8") (pintype "passive"))
      (node (ref "Q5") (pin "TH") (pinfunction "D_TH") (pintype "passive"))
      (node (ref "U$1") (pin "29") (pinfunction "PVDD1_29") (pintype "bidirectional"))
      (node (ref "U$1") (pin "53") (pinfunction "PVDD2_53") (pintype "bidirectional"))
      (node (ref "U$1") (pin "54") (pinfunction "PVDD2_54") (pintype "bidirectional"))
    )
    (net (code "5") (name "BST_A") (class "Default")
      (node (ref "C2") (pin "1") (pinfunction "1_1") (pintype "passive"))
      (node (ref "C42") (pin "1") (pinfunction "1_1") (pintype "passive"))
      (node (ref "U$1") (pin "48") (pinfunction "BST_A_48") (pintype "bidirectional"))
      (node (ref "U$2") (pin "1") (pinfunction "VDD1_1") (pintype "bidirectional"))
    )
    (net (code "6") (name "BST_B") (class "Default")
      (node (ref "C3") (pin "1") (pinfunction "1_1") (pintype "passive"))
      (node (ref "C43") (pin "1") (pinfunction "1_1") (pintype "passive"))
      (node (ref "U$1") (pin "43") (pinfunction "BST_B_43") (pintype "bidirectional"))
      (node (ref "U$3") (pin "1") (pinfunction "VDD1_1") (pintype "bidirectional"))
    )
    (net (code "7") (name "BST_C") (class "Default")
      (node (ref "C4") (pin "1") (pinfunction "1_1") (pintype "passive"))
      (node (ref "C44") (pin "1") (pinfunction "1_1") (pintype "passive"))
      (node (ref "U$1") (pin "38") (pinfunction "BST_C_38") (pintype "bidirectional"))
      (node (ref "U$4") (pin "1") (pinfunction "VDD1_1") (pintype "bidirectional"))
    )
    (net (code "8") (name "ENC_A") (class "Default")
      (node (ref "ENC_ABI") (pin "2") (pinfunction "S_2") (pintype "passive"))
      (node (ref "STM32F405_64") (pin "29") (pinfunction "PORTB_10_29") (pintype "bidirectional"))
    )
    (net (code "9") (name "ENC_B") (class "Default")
      (node (ref "ENC_ABI") (pin "3") (pinfunction "S_3") (pintype "passive"))
      (node (ref "STM32F405_64") (pin "17") (pinfunction "PORTA_3_17") (pintype "bidirectional"))
    )
    (net (code "10") (name "ENC_I") (class "Default")
      (node (ref "ENC_ABI") (pin "4") (pinfunction "S_4") (pintype "passive"))
      (node (ref "STM32F405_64") (pin "20") (pinfunction "PORTA_4_20") (pintype "bidirectional"))
    )
    (net (code "11") (name "ENC_MISO") (class "Default")
      (node (ref "ENCODER_SPI") (pin "2") (pinfunction "S_2") (pintype "passive"))
      (node (ref "STM32F405_64") (pin "22") (pinfunction "PORTA_6_22") (pintype "bidirectional"))
    )
    (net (code "12") (name "ENC_MOSI") (class "Default")
      (node (ref "ENCODER_SPI") (pin "3") (pinfunction "S_3") (pintype "passive"))
      (node (ref "STM32F405_64") (pin "57") (pinfunction "PORTB_5_57") (pintype "bidirectional"))
    )
    (net (code "13") (name "ENC_SCLK") (class "Default")
      (node (ref "ENCODER_SPI") (pin "4") (pinfunction "S_4") (pintype "passive"))
      (node (ref "STM32F405_64") (pin "21") (pinfunction "PORTA_5_21") (pintype "bidirectional"))
    )
    (net (code "14") (name "EN_GATE") (class "Default")
      (node (ref "STM32F405_64") (pin "41") (pinfunction "PORTA_8_41") (pintype "bidirectional"))
      (node (ref "U$1") (pin "16") (pinfunction "EN_GATE_16") (pintype "bidirectional"))
    )
    (net (code "15") (name "GD_MISO") (class "Default")
      (node (ref "STM32F405_64") (pin "35") (pinfunction "PORTB_14_35") (pintype "bidirectional"))
      (node (ref "U$1") (pin "10") (pinfunction "SDO_10") (pintype "bidirectional"))
    )
    (net (code "16") (name "GD_MOSI") (class "Default")
      (node (ref "STM32F405_64") (pin "36") (pinfunction "PORTB_15_36") (pintype "bidirectional"))
      (node (ref "U$1") (pin "9") (pinfunction "SDI_9") (pintype "bidirectional"))
    )
    (net (code "17") (name "GD_SCLK") (class "Default")
      (node (ref "STM32F405_64") (pin "34") (pinfunction "PORTB_13_34") (pintype "bidirectional"))
      (node (ref "U$1") (pin "11") (pinfunction "SCLK_11") (pintype "bidirectional"))
    )
    (net (code "18") (name "GH_A") (class "Default")
      (node (ref "R13") (pin "1") (pinfunction "1_1") (pintype "passive"))
      (node (ref "U$1") (pin "47") (pinfunction "GH_A_47") (pintype "bidirectional"))
    )
    (net (code "19") (name "GH_B") (class "Default")
      (node (ref "R14") (pin "1") (pinfunction "1_1") (pintype "passive"))
      (node (ref "U$1") (pin "42") (pinfunction "GH_B_42") (pintype "bidirectional"))
    )
    (net (code "20") (name "GH_C") (class "Default")
      (node (ref "R17") (pin "1") (pinfunction "1_1") (pintype "passive"))
      (node (ref "U$1") (pin "37") (pinfunction "GH_C_37") (pintype "bidirectional"))
    )
    (net (code "21") (name "GL_A") (class "Default")
      (node (ref "R12") (pin "1") (pinfunction "1_1") (pintype "passive"))
      (node (ref "U$1") (pin "45") (pinfunction "GL_A_45") (pintype "bidirectional"))
    )
    (net (code "22") (name "GL_B") (class "Default")
      (node (ref "R3") (pin "1") (pinfunction "1_1") (pintype "passive"))
      (node (ref "U$1") (pin "40") (pinfunction "GL_B_40") (pintype "bidirectional"))
    )
    (net (code "23") (name "GL_C") (class "Default")
      (node (ref "R16") (pin "1") (pinfunction "1_1") (pintype "passive"))
      (node (ref "U$1") (pin "35") (pinfunction "GL_C_35") (pintype "bidirectional"))
    )
    (net (code "24") (name "GND") (class "Default")
      (node (ref "BATTERY") (pin "1") (pinfunction "SK_1") (pintype "passive"))
      (node (ref "C1") (pin "1") (pinfunction "1_1") (pintype "passive"))
      (node (ref "C10") (pin "1") (pinfunction "1_1") (pintype "passive"))
      (node (ref "C11") (pin "1") (pinfunction "1_1") (pintype "passive"))
      (node (ref "C14") (pin "-") (pinfunction "-_-") (pintype "passive"))
      (node (ref "C15") (pin "-") (pinfunction "-_-") (pintype "passive"))
      (node (ref "C17") (pin "2") (pinfunction "2_2") (pintype "passive"))
      (node (ref "C18") (pin "2") (pinfunction "2_2") (pintype "passive"))
      (node (ref "C19") (pin "2") (pinfunction "2_2") (pintype "passive"))
      (node (ref "C20") (pin "2") (pinfunction "2_2") (pintype "passive"))
      (node (ref "C21") (pin "2") (pinfunction "2_2") (pintype "passive"))
      (node (ref "C22") (pin "2") (pinfunction "2_2") (pintype "passive"))
      (node (ref "C23") (pin "2") (pinfunction "2_2") (pintype "passive"))
      (node (ref "C24") (pin "1") (pinfunction "1_1") (pintype "passive"))
      (node (ref "C25") (pin "1") (pinfunction "1_1") (pintype "passive"))
      (node (ref "C26") (pin "1") (pinfunction "1_1") (pintype "passive"))
      (node (ref "C27") (pin "1") (pinfunction "1_1") (pintype "passive"))
      (node (ref "C28") (pin "1") (pinfunction "1_1") (pintype "passive"))
      (node (ref "C29") (pin "1") (pinfunction "1_1") (pintype "passive"))
      (node (ref "C30") (pin "1") (pinfunction "1_1") (pintype "passive"))
      (node (ref "C31") (pin "1") (pinfunction "1_1") (pintype "passive"))
      (node (ref "C32") (pin "1") (pinfunction "1_1") (pintype "passive"))
      (node (ref "C33") (pin "1") (pinfunction "1_1") (pintype "passive"))
      (node (ref "C37") (pin "2") (pinfunction "2_2") (pintype "passive"))
      (node (ref "C38") (pin "2") (pinfunction "2_2") (pintype "passive"))
      (node (ref "C45") (pin "2") (pinfunction "2_2") (pintype "passive"))
      (node (ref "C46") (pin "2") (pinfunction "2_2") (pintype "passive"))
      (node (ref "C47") (pin "2") (pinfunction "2_2") (pintype "passive"))
      (node (ref "C48") (pin "2") (pinfunction "2_2") (pintype "passive"))
      (node (ref "C5") (pin "1") (pinfunction "1_1") (pintype "passive"))
      (node (ref "C7") (pin "2") (pinfunction "2_2") (pintype "passive"))
      (node (ref "C9") (pin "1") (pinfunction "1_1") (pintype "passive"))
      (node (ref "D1") (pin "A") (pinfunction "A_A") (pintype "passive"))
      (node (ref "ENCODER_SPI") (pin "5") (pinfunction "S_5") (pintype "passive"))
      (node (ref "ENC_ABI") (pin "5") (pinfunction "S_5") (pintype "passive"))
      (node (ref "ERROR") (pin "C") (pinfunction "C_C") (pintype "passive"))
      (node (ref "IC1") (pin "2") (pinfunction "GND_2") (pintype "power_in"))
      (node (ref "MASTER_SPI") (pin "5") (pinfunction "S_5") (pintype "passive"))
      (node (ref "Q2") (pin "1") (pinfunction "S_1") (pintype "passive"))
      (node (ref "Q2") (pin "2") (pinfunction "S_2") (pintype "passive"))
      (node (ref "Q2") (pin "3") (pinfunction "S_3") (pintype "passive"))
      (node (ref "Q4") (pin "1") (pinfunction "S_1") (pintype "passive"))
      (node (ref "Q4") (pin "2") (pinfunction "S_2") (pintype "passive"))
      (node (ref "Q4") (pin "3") (pinfunction "S_3") (pintype "passive"))
      (node (ref "Q6") (pin "1") (pinfunction "S_1") (pintype "passive"))
      (node (ref "Q6") (pin "2") (pinfunction "S_2") (pintype "passive"))
      (node (ref "Q6") (pin "3") (pinfunction "S_3") (pintype "passive"))
      (node (ref "QG1") (pin "P$2") (pinfunction "GND_P$2") (pintype "power_in"))
      (node (ref "R24") (pin "2") (pinfunction "2_2") (pintype "passive"))
      (node (ref "R27") (pin "1") (pinfunction "1_1") (pintype "passive"))
      (node (ref "R28") (pin "1") (pinfunction "1_1") (pintype "passive"))
      (node (ref "R29") (pin "1") (pinfunction "1_1") (pintype "passive"))
      (node (ref "R5") (pin "1") (pinfunction "1_1") (pintype "passive"))
      (node (ref "R9") (pin "1") (pinfunction "1_1") (pintype "passive"))
      (node (ref "RESET") (pin "1") (pinfunction "1_1") (pintype "passive"))
      (node (ref "STM32F405_64") (pin "12") (pinfunction "VSSA_12") (pintype "bidirectional"))
      (node (ref "STM32F405_64") (pin "18") (pinfunction "VSS_18") (pintype "bidirectional"))
      (node (ref "STM32F405_64") (pin "63") (pinfunction "VSS_63") (pintype "bidirectional"))
      (node (ref "SW1") (pin "1") (pinfunction "1_1") (pintype "passive"))
      (node (ref "SW2") (pin "1") (pinfunction "1_1") (pintype "passive"))
      (node (ref "SWD") (pin "3") (pinfunction "3_3") (pintype "passive"))
      (node (ref "U$1") (pin "12") (pinfunction "DC_CAL_12") (pintype "bidirectional"))
      (node (ref "U$1") (pin "24") (pinfunction "REF_24") (pintype "bidirectional"))
      (node (ref "U$1") (pin "28") (pinfunction "AGND_28") (pintype "bidirectional"))
      (node (ref "U$1") (pin "30") (pinfunction "SP2_30") (pintype "bidirectional"))
      (node (ref "U$1") (pin "31") (pinfunction "SN2_31") (pintype "bidirectional"))
      (node (ref "U$1") (pin "32") (pinfunction "SP1_32") (pintype "bidirectional"))
      (node (ref "U$1") (pin "33") (pinfunction "SN1_33") (pintype "bidirectional"))
      (node (ref "U$1") (pin "34") (pinfunction "SL_C_34") (pintype "bidirectional"))
      (node (ref "U$1") (pin "39") (pinfunction "SL_B_39") (pintype "bidirectional"))
      (node (ref "U$1") (pin "44") (pinfunction "SL_A_44") (pintype "bidirectional"))
      (node (ref "U$1") (pin "7") (pinfunction "DTC_7") (pintype "bidirectional"))
      (node (ref "U$1") (pin "8") (pinfunction "~{SCS}_8") (pintype "bidirectional"))
      (node (ref "U$1") (pin "EXP@1") (pinfunction "GND_PAD_EXP@1") (pintype "bidirectional"))
      (node (ref "U$1") (pin "EXP@2") (pinfunction "GND_PAD_EXP@2") (pintype "bidirectional"))
      (node (ref "U$2") (pin "5") (pinfunction "GND2_5") (pintype "bidirectional"))
      (node (ref "U$3") (pin "5") (pinfunction "GND2_5") (pintype "bidirectional"))
      (node (ref "U$4") (pin "5") (pinfunction "GND2_5") (pintype "bidirectional"))
      (node (ref "USB") (pin "5") (pinfunction "5_5") (pintype "passive"))
    )
    (net (code "25") (name "H_A") (class "Default")
      (node (ref "STM32F405_64") (pin "37") (pinfunction "PORTC_6_37") (pintype "bidirectional"))
      (node (ref "U$1") (pin "17") (pinfunction "INH_A_17") (pintype "bidirectional"))
    )
    (net (code "26") (name "H_B") (class "Default")
      (node (ref "STM32F405_64") (pin "38") (pinfunction "PORTC_7_38") (pintype "bidirectional"))
      (node (ref "U$1") (pin "19") (pinfunction "INH_B_19") (pintype "bidirectional"))
    )
    (net (code "27") (name "H_C") (class "Default")
      (node (ref "STM32F405_64") (pin "39") (pinfunction "PORTC_8_39") (pintype "bidirectional"))
      (node (ref "U$1") (pin "21") (pinfunction "INH_C_21") (pintype "bidirectional"))
    )
    (net (code "28") (name "I_A") (class "Default")
      (node (ref "STM32F405_64") (pin "14") (pinfunction "PORTA_0_14") (pintype "bidirectional"))
      (node (ref "U$2") (pin "7") (pinfunction "VOUTP_7") (pintype "bidirectional"))
    )
    (net (code "29") (name "I_B") (class "Default")
      (node (ref "STM32F405_64") (pin "15") (pinfunction "PORTA_1_15") (pintype "bidirectional"))
      (node (ref "U$3") (pin "7") (pinfunction "VOUTP_7") (pintype "bidirectional"))
    )
    (net (code "30") (name "I_C") (class "Default")
      (node (ref "STM32F405_64") (pin "16") (pinfunction "PORTA_2_16") (pintype "bidirectional"))
      (node (ref "U$4") (pin "7") (pinfunction "VOUTP_7") (pintype "bidirectional"))
    )
    (net (code "31") (name "LED1") (class "Default")
      (node (ref "LED1") (pin "A") (pinfunction "A_A") (pintype "passive"))
      (node (ref "STM32F405_64") (pin "10") (pinfunction "PORTC_2_10") (pintype "bidirectional"))
    )
    (net (code "32") (name "LED2") (class "Default")
      (node (ref "LED2") (pin "A") (pinfunction "A_A") (pintype "passive"))
      (node (ref "STM32F405_64") (pin "11") (pinfunction "PORTC_3_11") (pintype "bidirectional"))
    )
    (net (code "33") (name "LED_ERROR") (class "Default")
      (node (ref "R26") (pin "2") (pinfunction "2_2") (pintype "passive"))
      (node (ref "STM32F405_64") (pin "2") (pinfunction "PORTC_13_2") (pintype "bidirectional"))
    )
    (net (code "34") (name "L_A") (class "Default")
      (node (ref "STM32F405_64") (pin "23") (pinfunction "PORTA_7_23") (pintype "bidirectional"))
      (node (ref "U$1") (pin "18") (pinfunction "INL_A_18") (pintype "bidirectional"))
    )
    (net (code "35") (name "L_B") (class "Default")
      (node (ref "STM32F405_64") (pin "26") (pinfunction "PORTB_0_26") (pintype "bidirectional"))
      (node (ref "U$1") (pin "20") (pinfunction "INL_B_20") (pintype "bidirectional"))
    )
    (net (code "36") (name "L_C") (class "Default")
      (node (ref "STM32F405_64") (pin "27") (pinfunction "PORTB_1_27") (pintype "bidirectional"))
      (node (ref "U$1") (pin "22") (pinfunction "INL_C_22") (pintype "bidirectional"))
    )
    (net (code "37") (name "MSTR_MISO") (class "Default")
      (node (ref "MASTER_SPI") (pin "2") (pinfunction "S_2") (pintype "passive"))
      (node (ref "STM32F405_64") (pin "52") (pinfunction "PORTC_11_52") (pintype "bidirectional"))
    )
    (net (code "38") (name "MSTR_MOSI") (class "Default")
      (node (ref "MASTER_SPI") (pin "3") (pinfunction "S_3") (pintype "passive"))
      (node (ref "STM32F405_64") (pin "53") (pinfunction "PORTC_12_53") (pintype "bidirectional"))
    )
    (net (code "39") (name "MSTR_SCLK") (class "Default")
      (node (ref "MASTER_SPI") (pin "4") (pinfunction "S_4") (pintype "passive"))
      (node (ref "STM32F405_64") (pin "51") (pinfunction "PORTC_10_51") (pintype "bidirectional"))
    )
    (net (code "40") (name "Net-(C8-Pad2)") (class "Default")
      (node (ref "C8") (pin "2") (pinfunction "2_2") (pintype "passive"))
      (node (ref "D1") (pin "C") (pinfunction "C_C") (pintype "passive"))
      (node (ref "L1") (pin "1") (pinfunction "1_1") (pintype "passive"))
      (node (ref "U$1") (pin "50") (pinfunction "PH_50") (pintype "bidirectional"))
      (node (ref "U$1") (pin "51") (pinfunction "PH_51") (pintype "bidirectional"))
    )
    (net (code "41") (name "Net-(C11-Pad2)") (class "Default")
      (node (ref "C11") (pin "2") (pinfunction "2_2") (pintype "passive"))
      (node (ref "R11") (pin "1") (pinfunction "1_1") (pintype "passive"))
    )
    (net (code "42") (name "Net-(ERROR-PadA)") (class "Default")
      (node (ref "ERROR") (pin "A") (pinfunction "A_A") (pintype "passive"))
      (node (ref "R26") (pin "1") (pinfunction "1_1") (pintype "passive"))
    )
    (net (code "43") (name "Net-(IC1A-IN)") (class "Default")
      (node (ref "C22") (pin "1") (pinfunction "1_1") (pintype "passive"))
      (node (ref "D2") (pin "C") (pinfunction "C_C") (pintype "passive"))
      (node (ref "D3") (pin "C") (pinfunction "C_C") (pintype "passive"))
      (node (ref "D4") (pin "C") (pinfunction "C_C") (pintype "passive"))
      (node (ref "IC1") (pin "1") (pinfunction "IN_1") (pintype "input"))
    )
    (net (code "44") (name "Net-(L2-Pad1)") (class "Default")
      (node (ref "L2") (pin "1") (pinfunction "1_1") (pintype "passive"))
      (node (ref "R4") (pin "1") (pinfunction "1_1") (pintype "passive"))
    )
    (net (code "45") (name "Net-(LED1-PadC)") (class "Default")
      (node (ref "LED1") (pin "C") (pinfunction "C_C") (pintype "passive"))
      (node (ref "R27") (pin "2") (pinfunction "2_2") (pintype "passive"))
    )
    (net (code "46") (name "Net-(LED2-PadC)") (class "Default")
      (node (ref "LED2") (pin "C") (pinfunction "C_C") (pintype "passive"))
      (node (ref "R28") (pin "2") (pinfunction "2_2") (pintype "passive"))
    )
    (net (code "47") (name "Net-(Q1-G)") (class "Default")
      (node (ref "Q1") (pin "4") (pinfunction "G_4") (pintype "passive"))
      (node (ref "R13") (pin "2") (pinfunction "2_2") (pintype "passive"))
    )
    (net (code "48") (name "Net-(Q2-G)") (class "Default")
      (node (ref "Q2") (pin "4") (pinfunction "G_4") (pintype "passive"))
      (node (ref "R12") (pin "2") (pinfunction "2_2") (pintype "passive"))
    )
    (net (code "49") (name "Net-(Q3-G)") (class "Default")
      (node (ref "Q3") (pin "4") (pinfunction "G_4") (pintype "passive"))
      (node (ref "R14") (pin "2") (pinfunction "2_2") (pintype "passive"))
    )
    (net (code "50") (name "Net-(Q4-G)") (class "Default")
      (node (ref "Q4") (pin "4") (pinfunction "G_4") (pintype "passive"))
      (node (ref "R3") (pin "2") (pinfunction "2_2") (pintype "passive"))
    )
    (net (code "51") (name "Net-(Q5-G)") (class "Default")
      (node (ref "Q5") (pin "4") (pinfunction "G_4") (pintype "passive"))
      (node (ref "R17") (pin "2") (pinfunction "2_2") (pintype "passive"))
    )
    (net (code "52") (name "Net-(Q6-G)") (class "Default")
      (node (ref "Q6") (pin "4") (pinfunction "G_4") (pintype "passive"))
      (node (ref "R16") (pin "2") (pinfunction "2_2") (pintype "passive"))
    )
    (net (code "53") (name "Net-(QG1-FO)") (class "Default")
      (node (ref "QG1") (pin "P$3") (pinfunction "FO_P$3") (pintype "output"))
      (node (ref "STM32F405_64") (pin "5") (pinfunction "PORTH_0_5") (pintype "bidirectional"))
    )
    (net (code "54") (name "Net-(STM32F405_64A-BOOT0)") (class "Default")
      (node (ref "R24") (pin "1") (pinfunction "1_1") (pintype "passive"))
      (node (ref "STM32F405_64") (pin "60") (pinfunction "BOOT0_60") (pintype "bidirectional"))
    )
    (net (code "55") (name "Net-(STM32F405_64A-VCAP_1)") (class "Default")
      (node (ref "C27") (pin "2") (pinfunction "2_2") (pintype "passive"))
      (node (ref "STM32F405_64") (pin "31") (pinfunction "VCAP_1_31") (pintype "bidirectional"))
    )
    (net (code "56") (name "Net-(STM32F405_64A-VCAP_2)") (class "Default")
      (node (ref "C26") (pin "2") (pinfunction "2_2") (pintype "passive"))
      (node (ref "STM32F405_64") (pin "47") (pinfunction "VCAP_2_47") (pintype "bidirectional"))
    )
    (net (code "57") (name "Net-(U$1-AVDD)") (class "Default")
      (node (ref "C5") (pin "2") (pinfunction "2_2") (pintype "passive"))
      (node (ref "U$1") (pin "27") (pinfunction "AVDD_27") (pintype "bidirectional"))
    )
    (net (code "58") (name "Net-(U$1-BST_BK)") (class "Default")
      (node (ref "C8") (pin "1") (pinfunction "1_1") (pintype "passive"))
      (node (ref "U$1") (pin "52") (pinfunction "BST_BK_52") (pintype "bidirectional"))
    )
    (net (code "59") (name "Net-(U$1-COMP)") (class "Default")
      (node (ref "C10") (pin "2") (pinfunction "2_2") (pintype "passive"))
      (node (ref "R11") (pin "2") (pinfunction "2_2") (pintype "passive"))
      (node (ref "U$1") (pin "2") (pinfunction "COMP_2") (pintype "bidirectional"))
    )
    (net (code "60") (name "Net-(U$1-CP1)") (class "Default")
      (node (ref "C6") (pin "1") (pinfunction "1_1") (pintype "passive"))
      (node (ref "U$1") (pin "14") (pinfunction "CP1_14") (pintype "bidirectional"))
    )
    (net (code "61") (name "Net-(U$1-CP2)") (class "Default")
      (node (ref "C6") (pin "2") (pinfunction "2_2") (pintype "passive"))
      (node (ref "U$1") (pin "15") (pinfunction "CP2_15") (pintype "bidirectional"))
    )
    (net (code "62") (name "Net-(U$1-DVDD)") (class "Default")
      (node (ref "C1") (pin "2") (pinfunction "2_2") (pintype "passive"))
      (node (ref "U$1") (pin "23") (pinfunction "DVDD_23") (pintype "bidirectional"))
    )
    (net (code "63") (name "Net-(U$1-GVDD)") (class "Default")
      (node (ref "C7") (pin "1") (pinfunction "1_1") (pintype "passive"))
      (node (ref "U$1") (pin "13") (pinfunction "GVDD_13") (pintype "bidirectional"))
    )
    (net (code "64") (name "Net-(U$1-RT_CLK)") (class "Default")
      (node (ref "R5") (pin "2") (pinfunction "2_2") (pintype "passive"))
      (node (ref "U$1") (pin "1") (pinfunction "RT_CLK_1") (pintype "bidirectional"))
    )
    (net (code "65") (name "Net-(U$1-SS_TR)") (class "Default")
      (node (ref "C9") (pin "2") (pinfunction "2_2") (pintype "passive"))
      (node (ref "U$1") (pin "56") (pinfunction "SS_TR_56") (pintype "bidirectional"))
    )
    (net (code "66") (name "Net-(U$1-VSENSE)") (class "Default")
      (node (ref "R10") (pin "1") (pinfunction "1_1") (pintype "passive"))
      (node (ref "R9") (pin "2") (pinfunction "2_2") (pintype "passive"))
      (node (ref "U$1") (pin "3") (pinfunction "VSENSE_3") (pintype "bidirectional"))
    )
    (net (code "67") (name "Net-(U$2-VINN)") (class "Default")
      (node (ref "C39") (pin "1") (pinfunction "1_1") (pintype "passive"))
      (node (ref "R30") (pin "2") (pinfunction "2_2") (pintype "passive"))
      (node (ref "U$2") (pin "3") (pinfunction "VINN_3") (pintype "bidirectional"))
    )
    (net (code "68") (name "Net-(U$2-VINP)") (class "Default")
      (node (ref "C39") (pin "2") (pinfunction "2_2") (pintype "passive"))
      (node (ref "R31") (pin "2") (pinfunction "2_2") (pintype "passive"))
      (node (ref "U$2") (pin "2") (pinfunction "VINP_2") (pintype "bidirectional"))
    )
    (net (code "69") (name "Net-(U$3-VINN)") (class "Default")
      (node (ref "C40") (pin "2") (pinfunction "2_2") (pintype "passive"))
      (node (ref "R33") (pin "2") (pinfunction "2_2") (pintype "passive"))
      (node (ref "U$3") (pin "3") (pinfunction "VINN_3") (pintype "bidirectional"))
    )
    (net (code "70") (name "Net-(U$3-VINP)") (class "Default")
      (node (ref "C40") (pin "1") (pinfunction "1_1") (pintype "passive"))
      (node (ref "R32") (pin "2") (pinfunction "2_2") (pintype "passive"))
      (node (ref "U$3") (pin "2") (pinfunction "VINP_2") (pintype "bidirectional"))
    )
    (net (code "71") (name "Net-(U$4-VINN)") (class "Default")
      (node (ref "C41") (pin "1") (pinfunction "1_1") (pintype "passive"))
      (node (ref "R34") (pin "2") (pinfunction "2_2") (pintype "passive"))
      (node (ref "U$4") (pin "3") (pinfunction "VINN_3") (pintype "bidirectional"))
    )
    (net (code "72") (name "Net-(U$4-VINP)") (class "Default")
      (node (ref "C41") (pin "2") (pinfunction "2_2") (pintype "passive"))
      (node (ref "R35") (pin "2") (pinfunction "2_2") (pintype "passive"))
      (node (ref "U$4") (pin "2") (pinfunction "VINP_2") (pintype "bidirectional"))
    )
    (net (code "73") (name "PWRGD") (class "Default")
      (node (ref "R8") (pin "1") (pinfunction "1_1") (pintype "passive"))
      (node (ref "U$1") (pin "4") (pinfunction "PWRGD_4") (pintype "bidirectional"))
    )
    (net (code "74") (name "RESET") (class "Default")
      (node (ref "C37") (pin "1") (pinfunction "1_1") (pintype "passive"))
      (node (ref "R25") (pin "1") (pinfunction "1_1") (pintype "passive"))
      (node (ref "RESET") (pin "3") (pinfunction "2_3") (pintype "passive"))
      (node (ref "STM32F405_64") (pin "7") (pinfunction "~{RST}_7") (pintype "bidirectional"))
      (node (ref "SWD") (pin "5") (pinfunction "5_5") (pintype "passive"))
    )
    (net (code "75") (name "SH_A") (class "Default")
      (node (ref "C2") (pin "2") (pinfunction "2_2") (pintype "passive"))
      (node (ref "C42") (pin "2") (pinfunction "2_2") (pintype "passive"))
      (node (ref "Q1") (pin "1") (pinfunction "S_1") (pintype "passive"))
      (node (ref "Q1") (pin "2") (pinfunction "S_2") (pintype "passive"))
      (node (ref "Q1") (pin "3") (pinfunction "S_3") (pintype "passive"))
      (node (ref "Q2") (pin "5") (pinfunction "D_5") (pintype "passive"))
      (node (ref "Q2") (pin "6") (pinfunction "D_6") (pintype "passive"))
      (node (ref "Q2") (pin "7") (pinfunction "D_7") (pintype "passive"))
      (node (ref "Q2") (pin "8") (pinfunction "D_8") (pintype "passive"))
      (node (ref "Q2") (pin "TH") (pinfunction "D_TH") (pintype "passive"))
      (node (ref "R1") (pin "2") (pinfunction "2_2") (pintype "passive"))
      (node (ref "R30") (pin "1") (pinfunction "1_1") (pintype "passive"))
      (node (ref "U$1") (pin "46") (pinfunction "SH_A_46") (pintype "bidirectional"))
      (node (ref "U$2") (pin "4") (pinfunction "GND1_4") (pintype "bidirectional"))
    )
    (net (code "76") (name "SH_B") (class "Default")
      (node (ref "C3") (pin "2") (pinfunction "2_2") (pintype "passive"))
      (node (ref "C43") (pin "2") (pinfunction "2_2") (pintype "passive"))
      (node (ref "Q3") (pin "1") (pinfunction "S_1") (pintype "passive"))
      (node (ref "Q3") (pin "2") (pinfunction "S_2") (pintype "passive"))
      (node (ref "Q3") (pin "3") (pinfunction "S_3") (pintype "passive"))
      (node (ref "Q4") (pin "5") (pinfunction "D_5") (pintype "passive"))
      (node (ref "Q4") (pin "6") (pinfunction "D_6") (pintype "passive"))
      (node (ref "Q4") (pin "7") (pinfunction "D_7") (pintype "passive"))
      (node (ref "Q4") (pin "8") (pinfunction "D_8") (pintype "passive"))
      (node (ref "Q4") (pin "TH") (pinfunction "D_TH") (pintype "passive"))
      (node (ref "R2") (pin "2") (pinfunction "2_2") (pintype "passive"))
      (node (ref "R32") (pin "1") (pinfunction "1_1") (pintype "passive"))
      (node (ref "U$1") (pin "41") (pinfunction "SH_B_41") (pintype "bidirectional"))
      (node (ref "U$3") (pin "4") (pinfunction "GND1_4") (pintype "bidirectional"))
    )
    (net (code "77") (name "SH_C") (class "Default")
      (node (ref "C4") (pin "2") (pinfunction "2_2") (pintype "passive"))
      (node (ref "C44") (pin "2") (pinfunction "2_2") (pintype "passive"))
      (node (ref "Q5") (pin "1") (pinfunction "S_1") (pintype "passive"))
      (node (ref "Q5") (pin "2") (pinfunction "S_2") (pintype "passive"))
      (node (ref "Q5") (pin "3") (pinfunction "S_3") (pintype "passive"))
      (node (ref "Q6") (pin "5") (pinfunction "D_5") (pintype "passive"))
      (node (ref "Q6") (pin "6") (pinfunction "D_6") (pintype "passive"))
      (node (ref "Q6") (pin "7") (pinfunction "D_7") (pintype "passive"))
      (node (ref "Q6") (pin "8") (pinfunction "D_8") (pintype "passive"))
      (node (ref "Q6") (pin "TH") (pinfunction "D_TH") (pintype "passive"))
      (node (ref "R15") (pin "2") (pinfunction "2_2") (pintype "passive"))
      (node (ref "R34") (pin "1") (pinfunction "1_1") (pintype "passive"))
      (node (ref "U$1") (pin "36") (pinfunction "SH_C_36") (pintype "bidirectional"))
      (node (ref "U$4") (pin "4") (pinfunction "GND1_4") (pintype "bidirectional"))
    )
    (net (code "78") (name "SW1") (class "Default")
      (node (ref "STM32F405_64") (pin "8") (pinfunction "PORTC_0_8") (pintype "bidirectional"))
      (node (ref "SW1") (pin "3") (pinfunction "2_3") (pintype "passive"))
    )
    (net (code "79") (name "SW2") (class "Default")
      (node (ref "STM32F405_64") (pin "9") (pinfunction "PORTC_1_9") (pintype "bidirectional"))
      (node (ref "SW2") (pin "3") (pinfunction "2_3") (pintype "passive"))
    )
    (net (code "80") (name "SWCLK") (class "Default")
      (node (ref "STM32F405_64") (pin "49") (pinfunction "PORTA_14_49") (pintype "bidirectional"))
      (node (ref "SWD") (pin "2") (pinfunction "2_2") (pintype "passive"))
    )
    (net (code "81") (name "SWDIO") (class "Default")
      (node (ref "STM32F405_64") (pin "46") (pinfunction "PORTA_13_46") (pintype "bidirectional"))
      (node (ref "SWD") (pin "4") (pinfunction "4_4") (pintype "passive"))
    )
    (net (code "82") (name "SWO") (class "Default")
      (node (ref "STM32F405_64") (pin "55") (pinfunction "PORTB_3_55") (pintype "bidirectional"))
      (node (ref "SWD") (pin "6") (pinfunction "6_6") (pintype "passive"))
    )
    (net (code "83") (name "USB_DM") (class "Default")
      (node (ref "STM32F405_64") (pin "44") (pinfunction "PORTA_11_44") (pintype "bidirectional"))
      (node (ref "USB") (pin "2") (pinfunction "2_2") (pintype "passive"))
    )
    (net (code "84") (name "USB_DP") (class "Default")
      (node (ref "STM32F405_64") (pin "45") (pinfunction "PORTA_12_45") (pintype "bidirectional"))
      (node (ref "USB") (pin "3") (pinfunction "3_3") (pintype "passive"))
    )
    (net (code "85") (name "USB_ID") (class "Default")
      (node (ref "STM32F405_64") (pin "43") (pinfunction "PORTA_10_43") (pintype "bidirectional"))
      (node (ref "USB") (pin "4") (pinfunction "4_4") (pintype "passive"))
    )
    (net (code "86") (name "USB_VBUS") (class "Default")
      (node (ref "D4") (pin "A") (pinfunction "A_A") (pintype "passive"))
      (node (ref "STM32F405_64") (pin "42") (pinfunction "PORTA_9_42") (pintype "bidirectional"))
      (node (ref "USB") (pin "1") (pinfunction "1_1") (pintype "passive"))
    )
    (net (code "87") (name "U_A") (class "Default")
      (node (ref "MOTOR") (pin "1") (pinfunction "KL_1") (pintype "passive"))
      (node (ref "R1") (pin "1") (pinfunction "1_1") (pintype "passive"))
      (node (ref "R31") (pin "1") (pinfunction "1_1") (pintype "passive"))
    )
    (net (code "88") (name "U_B") (class "Default")
      (node (ref "MOTOR") (pin "2") (pinfunction "KL_2") (pintype "passive"))
      (node (ref "R2") (pin "1") (pinfunction "1_1") (pintype "passive"))
      (node (ref "R33") (pin "1") (pinfunction "1_1") (pintype "passive"))
    )
    (net (code "89") (name "U_C") (class "Default")
      (node (ref "MOTOR") (pin "3") (pinfunction "KL_3") (pintype "passive"))
      (node (ref "R15") (pin "1") (pinfunction "1_1") (pintype "passive"))
      (node (ref "R35") (pin "1") (pinfunction "1_1") (pintype "passive"))
    )
    (net (code "90") (name "VREF") (class "Default")
      (node (ref "C24") (pin "2") (pinfunction "2_2") (pintype "passive"))
      (node (ref "C25") (pin "2") (pinfunction "2_2") (pintype "passive"))
      (node (ref "C45") (pin "1") (pinfunction "1_1") (pintype "passive"))
      (node (ref "C46") (pin "1") (pinfunction "1_1") (pintype "passive"))
      (node (ref "C47") (pin "1") (pinfunction "1_1") (pintype "passive"))
      (node (ref "R4") (pin "2") (pinfunction "2_2") (pintype "passive"))
      (node (ref "STM32F405_64") (pin "13") (pinfunction "VDDA_13") (pintype "bidirectional"))
      (node (ref "U$2") (pin "8") (pinfunction "VDD2_8") (pintype "bidirectional"))
      (node (ref "U$3") (pin "8") (pinfunction "VDD2_8") (pintype "bidirectional"))
      (node (ref "U$4") (pin "8") (pinfunction "VDD2_8") (pintype "bidirectional"))
    )
    (net (code "91") (name "unconnected-(STM32F405_64B-PORTA_15-Pad50)") (class "Default")
      (node (ref "STM32F405_64") (pin "50") (pinfunction "PORTA_15_50") (pintype "bidirectional"))
    )
    (net (code "92") (name "unconnected-(STM32F405_64C-PORTB_2-Pad28)") (class "Default")
      (node (ref "STM32F405_64") (pin "28") (pinfunction "PORTB_2_28") (pintype "bidirectional"))
    )
    (net (code "93") (name "unconnected-(STM32F405_64C-PORTB_4-Pad56)") (class "Default")
      (node (ref "STM32F405_64") (pin "56") (pinfunction "PORTB_4_56") (pintype "bidirectional"))
    )
    (net (code "94") (name "unconnected-(STM32F405_64C-PORTB_6-Pad58)") (class "Default")
      (node (ref "STM32F405_64") (pin "58") (pinfunction "PORTB_6_58") (pintype "bidirectional"))
    )
    (net (code "95") (name "unconnected-(STM32F405_64C-PORTB_7-Pad59)") (class "Default")
      (node (ref "STM32F405_64") (pin "59") (pinfunction "PORTB_7_59") (pintype "bidirectional"))
    )
    (net (code "96") (name "unconnected-(STM32F405_64C-PORTB_8-Pad61)") (class "Default")
      (node (ref "STM32F405_64") (pin "61") (pinfunction "PORTB_8_61") (pintype "bidirectional"))
    )
    (net (code "97") (name "unconnected-(STM32F405_64C-PORTB_9-Pad62)") (class "Default")
      (node (ref "STM32F405_64") (pin "62") (pinfunction "PORTB_9_62") (pintype "bidirectional"))
    )
    (net (code "98") (name "unconnected-(STM32F405_64C-PORTB_11-Pad30)") (class "Default")
      (node (ref "STM32F405_64") (pin "30") (pinfunction "PORTB_11_30") (pintype "bidirectional"))
    )
    (net (code "99") (name "unconnected-(STM32F405_64C-PORTB_12-Pad33)") (class "Default")
      (node (ref "STM32F405_64") (pin "33") (pinfunction "PORTB_12_33") (pintype "bidirectional"))
    )
    (net (code "100") (name "unconnected-(STM32F405_64D-PORTC_4-Pad24)") (class "Default")
      (node (ref "STM32F405_64") (pin "24") (pinfunction "PORTC_4_24") (pintype "bidirectional"))
    )
    (net (code "101") (name "unconnected-(STM32F405_64D-PORTC_5-Pad25)") (class "Default")
      (node (ref "STM32F405_64") (pin "25") (pinfunction "PORTC_5_25") (pintype "bidirectional"))
    )
    (net (code "102") (name "unconnected-(STM32F405_64D-PORTC_9-Pad40)") (class "Default")
      (node (ref "STM32F405_64") (pin "40") (pinfunction "PORTC_9_40") (pintype "bidirectional"))
    )
    (net (code "103") (name "unconnected-(STM32F405_64D-PORTC_14-Pad3)") (class "Default")
      (node (ref "STM32F405_64") (pin "3") (pinfunction "PORTC_14_3") (pintype "bidirectional"))
    )
    (net (code "104") (name "unconnected-(STM32F405_64D-PORTC_15-Pad4)") (class "Default")
      (node (ref "STM32F405_64") (pin "4") (pinfunction "PORTC_15_4") (pintype "bidirectional"))
    )
    (net (code "105") (name "unconnected-(STM32F405_64E-PORTD_2-Pad54)") (class "Default")
      (node (ref "STM32F405_64") (pin "54") (pinfunction "PORTD_2_54") (pintype "bidirectional"))
    )
    (net (code "106") (name "unconnected-(STM32F405_64E-PORTH_1-Pad6)") (class "Default")
      (node (ref "STM32F405_64") (pin "6") (pinfunction "PORTH_1_6") (pintype "bidirectional"))
    )
    (net (code "107") (name "unconnected-(U$1-EN_BUCK-Pad55)") (class "Default")
      (node (ref "U$1") (pin "55") (pinfunction "EN_BUCK_55") (pintype "bidirectional"))
    )
    (net (code "108") (name "unconnected-(U$1-SO1-Pad25)") (class "Default")
      (node (ref "U$1") (pin "25") (pinfunction "SO1_25") (pintype "bidirectional"))
    )
    (net (code "109") (name "unconnected-(U$1-SO2-Pad26)") (class "Default")
      (node (ref "U$1") (pin "26") (pinfunction "SO2_26") (pintype "bidirectional"))
    )
    (net (code "110") (name "unconnected-(U$2-VOUTN-Pad6)") (class "Default")
      (node (ref "U$2") (pin "6") (pinfunction "VOUTN_6") (pintype "bidirectional"))
    )
    (net (code "111") (name "unconnected-(U$3-VOUTN-Pad6)") (class "Default")
      (node (ref "U$3") (pin "6") (pinfunction "VOUTN_6") (pintype "bidirectional"))
    )
    (net (code "112") (name "unconnected-(U$4-VOUTN-Pad6)") (class "Default")
      (node (ref "U$4") (pin "6") (pinfunction "VOUTN_6") (pintype "bidirectional"))
    )
    (net (code "113") (name "~{FAULT}") (class "Default")
      (node (ref "R7") (pin "1") (pinfunction "1_1") (pintype "passive"))
      (node (ref "U$1") (pin "6") (pinfunction "~{FAULT}_6") (pintype "bidirectional"))
    )
    (net (code "114") (name "~{OCTW}") (class "Default")
      (node (ref "R6") (pin "1") (pinfunction "1_1") (pintype "passive"))
      (node (ref "U$1") (pin "5") (pinfunction "~{OCTW}_5") (pintype "bidirectional"))
    )
  )
)
